# STM-Board-v1_1.net
KiCad netlist of a schematic drawn in Altium Designer
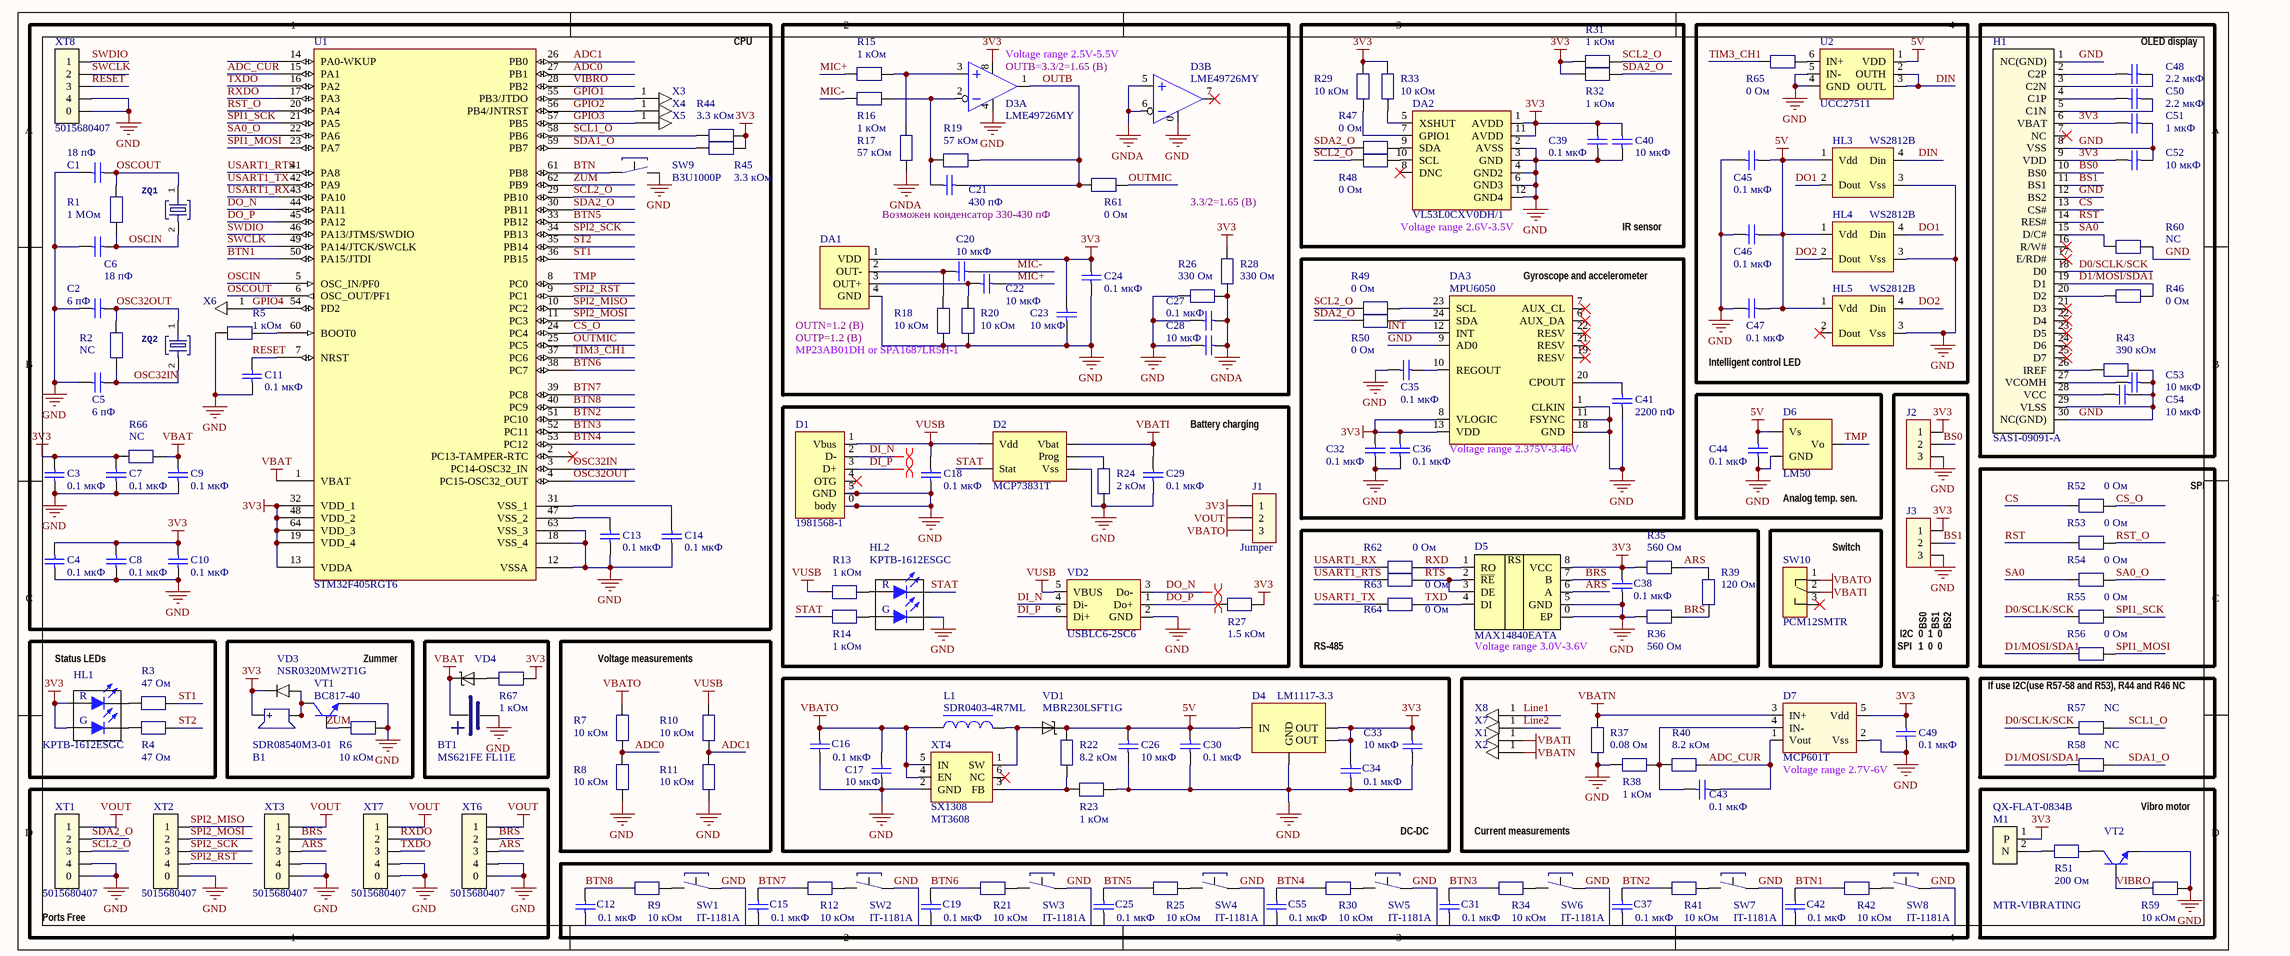
[diagram p0: STM-Board-v1.1.SchDoc]

(export (version "E")
  (design (tool "Eeschema 10.0.6"))
  (components
    (comp (ref "B1")
      (value "SDR08540M3-01")
      (footprint "SDR08540M3-01")
      (libsource (lib "dan") (part "SDR08540M3-01"))
    )
    (comp (ref "BT1")
      (value "MS621FE FL11E")
      (footprint "MS621FE FL11E")
      (libsource (lib "dan") (part "Battery RTC"))
    )
    (comp (ref "C1")
      (value "18 пФ")
      (footprint "C0402")
      (description "Чип конденсатор 0805")
      (fields (field (name "Comment") "Capacitor"))
      (libsource (lib "dan") (part "Capacitor"))
    )
    (comp (ref "C2")
      (value "6 пФ")
      (footprint "C0402")
      (description "Чип конденсатор 0805")
      (fields (field (name "Comment") "Capacitor"))
      (libsource (lib "dan") (part "Capacitor"))
    )
    (comp (ref "C3")
      (value "0.1 мкФ")
      (footprint "C0402")
      (description "Чип конденсатор 0805")
      (fields (field (name "Comment") "Capacitor"))
      (libsource (lib "dan") (part "Capacitor"))
    )
    (comp (ref "C4")
      (value "0.1 мкФ")
      (footprint "C0402")
      (description "Чип конденсатор 0805")
      (fields (field (name "Comment") "Capacitor"))
      (libsource (lib "dan") (part "Capacitor"))
    )
    (comp (ref "C5")
      (value "6 пФ")
      (footprint "C0402")
      (description "Чип конденсатор 0805")
      (fields (field (name "Comment") "Capacitor"))
      (libsource (lib "dan") (part "Capacitor"))
    )
    (comp (ref "C6")
      (value "18 пФ")
      (footprint "C0402")
      (description "Чип конденсатор 0805")
      (fields (field (name "Comment") "Capacitor"))
      (libsource (lib "dan") (part "Capacitor"))
    )
    (comp (ref "C7")
      (value "0.1 мкФ")
      (footprint "C0402")
      (description "Чип конденсатор 0805")
      (fields (field (name "Comment") "Capacitor"))
      (libsource (lib "dan") (part "Capacitor"))
    )
    (comp (ref "C8")
      (value "0.1 мкФ")
      (footprint "C0402")
      (description "Чип конденсатор 0805")
      (fields (field (name "Comment") "Capacitor"))
      (libsource (lib "dan") (part "Capacitor"))
    )
    (comp (ref "C9")
      (value "0.1 мкФ")
      (footprint "C0402")
      (description "Чип конденсатор 0805")
      (fields (field (name "Comment") "Capacitor"))
      (libsource (lib "dan") (part "Capacitor"))
    )
    (comp (ref "C10")
      (value "0.1 мкФ")
      (footprint "C0402")
      (description "Чип конденсатор 0805")
      (fields (field (name "Comment") "Capacitor"))
      (libsource (lib "dan") (part "Capacitor"))
    )
    (comp (ref "C11")
      (value "0.1 мкФ")
      (footprint "C0402")
      (description "Чип конденсатор 0805")
      (fields (field (name "Comment") "Capacitor"))
      (libsource (lib "dan") (part "Capacitor"))
    )
    (comp (ref "C12")
      (value "0.1 мкФ")
      (footprint "C0402")
      (description "Чип конденсатор 0805")
      (fields (field (name "Comment") "Capacitor"))
      (libsource (lib "dan") (part "Capacitor"))
    )
    (comp (ref "C13")
      (value "0.1 мкФ")
      (footprint "C0402")
      (description "Чип конденсатор 0805")
      (fields (field (name "Comment") "Capacitor"))
      (libsource (lib "dan") (part "Capacitor"))
    )
    (comp (ref "C14")
      (value "0.1 мкФ")
      (footprint "C0402")
      (description "Чип конденсатор 0805")
      (fields (field (name "Comment") "Capacitor"))
      (libsource (lib "dan") (part "Capacitor"))
    )
    (comp (ref "C15")
      (value "0.1 мкФ")
      (footprint "C0402")
      (description "Чип конденсатор 0805")
      (fields (field (name "Comment") "Capacitor"))
      (libsource (lib "dan") (part "Capacitor"))
    )
    (comp (ref "C16")
      (value "0.1 мкФ")
      (footprint "C0402")
      (description "Чип конденсатор 0805")
      (fields (field (name "Comment") "Capacitor"))
      (libsource (lib "dan") (part "Capacitor"))
    )
    (comp (ref "C17")
      (value "10 мкФ")
      (footprint "1206")
      (description "Чип конденсатор 0805")
      (fields (field (name "Comment") "Capacitor"))
      (libsource (lib "dan") (part "Capacitor"))
    )
    (comp (ref "C18")
      (value "0.1 мкФ")
      (footprint "C0402")
      (description "Чип конденсатор 0805")
      (fields (field (name "Comment") "Capacitor"))
      (libsource (lib "dan") (part "Capacitor"))
    )
    (comp (ref "C19")
      (value "0.1 мкФ")
      (footprint "C0402")
      (description "Чип конденсатор 0805")
      (fields (field (name "Comment") "Capacitor"))
      (libsource (lib "dan") (part "Capacitor"))
    )
    (comp (ref "C20")
      (value "10 мкФ")
      (footprint "C0402")
      (description "Чип конденсатор 0805")
      (fields (field (name "Comment") "Capacitor"))
      (libsource (lib "dan") (part "Capacitor"))
    )
    (comp (ref "C21")
      (value "430 пФ")
      (footprint "C0402")
      (description "Чип конденсатор 0805")
      (fields (field (name "Comment") "Capacitor"))
      (libsource (lib "dan") (part "Capacitor"))
    )
    (comp (ref "C22")
      (value "10 мкФ")
      (footprint "C0402")
      (description "Чип конденсатор 0805")
      (fields (field (name "Comment") "Capacitor"))
      (libsource (lib "dan") (part "Capacitor"))
    )
    (comp (ref "C23")
      (value "10 мкФ")
      (footprint "C0402")
      (description "Чип конденсатор 0805")
      (fields (field (name "Comment") "Capacitor"))
      (libsource (lib "dan") (part "Capacitor"))
    )
    (comp (ref "C24")
      (value "0.1 мкФ")
      (footprint "C0402")
      (description "Чип конденсатор 0805")
      (fields (field (name "Comment") "Capacitor"))
      (libsource (lib "dan") (part "Capacitor"))
    )
    (comp (ref "C25")
      (value "0.1 мкФ")
      (footprint "C0402")
      (description "Чип конденсатор 0805")
      (fields (field (name "Comment") "Capacitor"))
      (libsource (lib "dan") (part "Capacitor"))
    )
    (comp (ref "C26")
      (value "10 мкФ")
      (footprint "1206")
      (description "Чип конденсатор 0805")
      (fields (field (name "Comment") "Capacitor"))
      (libsource (lib "dan") (part "Capacitor"))
    )
    (comp (ref "C27")
      (value "0.1 мкФ")
      (footprint "C0402")
      (description "Чип конденсатор 0805")
      (fields (field (name "Comment") "Capacitor"))
      (libsource (lib "dan") (part "Capacitor"))
    )
    (comp (ref "C28")
      (value "10 мкФ")
      (footprint "C0402")
      (description "Чип конденсатор 0805")
      (fields (field (name "Comment") "Capacitor"))
      (libsource (lib "dan") (part "Capacitor"))
    )
    (comp (ref "C29")
      (value "0.1 мкФ")
      (footprint "C0402")
      (description "Чип конденсатор 0805")
      (fields (field (name "Comment") "Capacitor"))
      (libsource (lib "dan") (part "Capacitor"))
    )
    (comp (ref "C30")
      (value "0.1 мкФ")
      (footprint "C0402")
      (description "Чип конденсатор 0805")
      (fields (field (name "Comment") "Capacitor"))
      (libsource (lib "dan") (part "Capacitor"))
    )
    (comp (ref "C31")
      (value "0.1 мкФ")
      (footprint "C0402")
      (description "Чип конденсатор 0805")
      (fields (field (name "Comment") "Capacitor"))
      (libsource (lib "dan") (part "Capacitor"))
    )
    (comp (ref "C32")
      (value "0.1 мкФ")
      (footprint "C0402")
      (description "Чип конденсатор 0805")
      (fields (field (name "Comment") "Capacitor"))
      (libsource (lib "dan") (part "Capacitor"))
    )
    (comp (ref "C33")
      (value "10 мкФ")
      (footprint "1206")
      (description "Чип конденсатор 0805")
      (fields (field (name "Comment") "Capacitor"))
      (libsource (lib "dan") (part "Capacitor"))
    )
    (comp (ref "C34")
      (value "0.1 мкФ")
      (footprint "C0402")
      (description "Чип конденсатор 0805")
      (fields (field (name "Comment") "Capacitor"))
      (libsource (lib "dan") (part "Capacitor"))
    )
    (comp (ref "C35")
      (value "0.1 мкФ")
      (footprint "C0402")
      (description "Чип конденсатор 0805")
      (fields (field (name "Comment") "Capacitor"))
      (libsource (lib "dan") (part "Capacitor"))
    )
    (comp (ref "C36")
      (value "0.1 мкФ")
      (footprint "C0402")
      (description "Чип конденсатор 0805")
      (fields (field (name "Comment") "Capacitor"))
      (libsource (lib "dan") (part "Capacitor"))
    )
    (comp (ref "C37")
      (value "0.1 мкФ")
      (footprint "C0402")
      (description "Чип конденсатор 0805")
      (fields (field (name "Comment") "Capacitor"))
      (libsource (lib "dan") (part "Capacitor"))
    )
    (comp (ref "C38")
      (value "0.1 мкФ")
      (footprint "C0402")
      (description "Чип конденсатор 0805")
      (fields (field (name "Comment") "Capacitor"))
      (libsource (lib "dan") (part "Capacitor"))
    )
    (comp (ref "C39")
      (value "0.1 мкФ")
      (footprint "C0402")
      (description "Чип конденсатор 0805")
      (fields (field (name "Comment") "Capacitor"))
      (libsource (lib "dan") (part "Capacitor"))
    )
    (comp (ref "C40")
      (value "10 мкФ")
      (footprint "C0402")
      (description "Чип конденсатор 0805")
      (fields (field (name "Comment") "Capacitor"))
      (libsource (lib "dan") (part "Capacitor"))
    )
    (comp (ref "C41")
      (value "2200 пФ")
      (footprint "C0402")
      (description "Чип конденсатор 0805")
      (fields (field (name "Comment") "Capacitor"))
      (libsource (lib "dan") (part "Capacitor"))
    )
    (comp (ref "C42")
      (value "0.1 мкФ")
      (footprint "C0402")
      (description "Чип конденсатор 0805")
      (fields (field (name "Comment") "Capacitor"))
      (libsource (lib "dan") (part "Capacitor"))
    )
    (comp (ref "C43")
      (value "0.1 мкФ")
      (footprint "C0402")
      (description "Чип конденсатор 0805")
      (fields (field (name "Comment") "Capacitor"))
      (libsource (lib "dan") (part "Capacitor"))
    )
    (comp (ref "C44")
      (value "0.1 мкФ")
      (footprint "C0402")
      (description "Чип конденсатор 0805")
      (fields (field (name "Comment") "Capacitor"))
      (libsource (lib "dan") (part "Capacitor"))
    )
    (comp (ref "C45")
      (value "0.1 мкФ")
      (footprint "C0402")
      (description "Чип конденсатор 0805")
      (fields (field (name "Comment") "Capacitor"))
      (libsource (lib "dan") (part "Capacitor"))
    )
    (comp (ref "C46")
      (value "0.1 мкФ")
      (footprint "C0402")
      (description "Чип конденсатор 0805")
      (fields (field (name "Comment") "Capacitor"))
      (libsource (lib "dan") (part "Capacitor"))
    )
    (comp (ref "C47")
      (value "0.1 мкФ")
      (footprint "C0402")
      (description "Чип конденсатор 0805")
      (fields (field (name "Comment") "Capacitor"))
      (libsource (lib "dan") (part "Capacitor"))
    )
    (comp (ref "C48")
      (value "2.2 мкФ")
      (footprint "C0402")
      (description "Чип конденсатор 0805")
      (fields (field (name "Comment") "Capacitor"))
      (libsource (lib "dan") (part "Capacitor"))
    )
    (comp (ref "C49")
      (value "0.1 мкФ")
      (footprint "C0402")
      (description "Чип конденсатор 0805")
      (fields (field (name "Comment") "Capacitor"))
      (libsource (lib "dan") (part "Capacitor"))
    )
    (comp (ref "C50")
      (value "2.2 мкФ")
      (footprint "C0402")
      (description "Чип конденсатор 0805")
      (fields (field (name "Comment") "Capacitor"))
      (libsource (lib "dan") (part "Capacitor"))
    )
    (comp (ref "C51")
      (value "1 мкФ")
      (footprint "C0402")
      (description "Чип конденсатор 0805")
      (fields (field (name "Comment") "Capacitor"))
      (libsource (lib "dan") (part "Capacitor"))
    )
    (comp (ref "C52")
      (value "10 мкФ")
      (footprint "C0402")
      (description "Чип конденсатор 0805")
      (fields (field (name "Comment") "Capacitor"))
      (libsource (lib "dan") (part "Capacitor"))
    )
    (comp (ref "C53")
      (value "10 мкФ")
      (footprint "C0402")
      (description "Чип конденсатор 0805")
      (fields (field (name "Comment") "Capacitor"))
      (libsource (lib "dan") (part "Capacitor"))
    )
    (comp (ref "C54")
      (value "10 мкФ")
      (footprint "C0402")
      (description "Чип конденсатор 0805")
      (fields (field (name "Comment") "Capacitor"))
      (libsource (lib "dan") (part "Capacitor"))
    )
    (comp (ref "C55")
      (value "0.1 мкФ")
      (footprint "C0402")
      (description "Чип конденсатор 0805")
      (fields (field (name "Comment") "Capacitor"))
      (libsource (lib "dan") (part "Capacitor"))
    )
    (comp (ref "D1")
      (value "1981568-1")
      (footprint "MicroUSB-B")
      (description "micro")
      (libsource (lib "dan") (part "USB_micro"))
    )
    (comp (ref "D2") (value "MCP73831T") (footprint "SOT23-5") (libsource (lib "dan") (part "MCP73831")))
    (comp (ref "D3")
      (value "LME49726MY")
      (footprint "MSOP8 - PP")
      (description "Comparators")
      (fields (field (name "Comment") "Audio Operational Amplifier"))
      (libsource (lib "dan") (part "LME49726"))
    )
    (comp (ref "D4") (value "LM1117-3.3") (footprint "SOT223") (libsource (lib "dan") (part "LM1117")))
    (comp (ref "D5")
      (value "MAX14840EATA")
      (footprint "TDFN-8")
      (description "RS-485")
      (libsource (lib "dan") (part "MAX14840"))
    )
    (comp (ref "D6")
      (value "LM50")
      (footprint "SOT-23")
      (description "Temperatury sensors")
      (fields (field (name "Comment") "Датчик температуры"))
      (libsource (lib "dan") (part "LM50"))
    )
    (comp (ref "D7")
      (value "MCP601T")
      (footprint "SOT23-5")
      (fields (field (name "Comment") "Операционный усилитель"))
      (libsource (lib "dan") (part "MCP601T"))
    )
    (comp (ref "DA1")
      (value "MP23AB01DH or SPA1687LR5H-1")
      (footprint "MP23AB01DH")
      (libsource (lib "dan") (part "MP23AB01DH"))
    )
    (comp (ref "DA2")
      (value "VL53L0CXV0DH/1")
      (footprint "dan:VL53L0X - big")
      (fields (field (name "Comment") "ИК датчик VL53L0X"))
      (libsource (lib "dan") (part "VL53L0X"))
    )
    (comp (ref "DA3")
      (value "MPU6050")
      (footprint "MPU-6050")
      (fields (field (name "Comment") "Гироскоп"))
      (libsource (lib "dan") (part "MPU6050"))
    )
    (comp (ref "H1")
      (value "SAS1-09091-A")
      (footprint "OLED 1.3 128x64")
      (description "1.3in OLED 128x64  SAS1-09091-A")
      (fields (field (name "Comment") "OLED DIsp 1.3 128x64"))
      (libsource (lib "dan") (part "OLED_1.3_128x64"))
    )
    (comp (ref "HL1")
      (value "KPTB-1612ESGC")
      (footprint "LED_1.6x1.25")
      (libsource (lib "dan") (part "LED_x2_RG"))
    )
    (comp (ref "HL2")
      (value "KPTB-1612ESGC")
      (footprint "LED_1.6x1.25")
      (libsource (lib "dan") (part "LED_x2_RG"))
    )
    (comp (ref "HL3") (value "WS2812B") (footprint "WS2812B_N") (libsource (lib "dan") (part "WS2812B")))
    (comp (ref "HL4") (value "WS2812B") (footprint "WS2812B_N") (libsource (lib "dan") (part "WS2812B")))
    (comp (ref "HL5") (value "WS2812B") (footprint "WS2812B_N") (libsource (lib "dan") (part "WS2812B")))
    (comp (ref "J1")
      (value "Jumper")
      (footprint "Jumper_3")
      (fields (field (name "Comment") "Jumper_2"))
      (libsource (lib "") (part "Jumper_2_1"))
    )
    (comp (ref "J2")
      (value "Jumper_2")
      (footprint "Jumper_3")
      (description "Jumper")
      (libsource (lib "dan") (part "Jumper_2"))
    )
    (comp (ref "J3")
      (value "Jumper_2")
      (footprint "Jumper_3")
      (description "Jumper")
      (libsource (lib "dan") (part "Jumper_2"))
    )
    (comp (ref "L1") (value "SDR0403-4R7ML") (footprint "SDR0403") (libsource (lib "dan") (part "inductor")))
    (comp (ref "M1")
      (value "QX-FLAT-0834B")
      (footprint "QX-FLAT-0834B")
      (description "VIBRATING")
      (libsource (lib "dan") (part "QX-FLAT-0834B"))
    )
    (comp (ref "R1")
      (value "1 МОм")
      (footprint "R0402")
      (fields (field (name "Comment") "Чип резистор"))
      (libsource (lib "") (part "Resistor_2"))
    )
    (comp (ref "R2")
      (value "NC")
      (footprint "R0402")
      (fields (field (name "Comment") "Чип резистор"))
      (libsource (lib "") (part "Resistor_1"))
    )
    (comp (ref "R3")
      (value "47 Ом")
      (footprint "R0402")
      (fields (field (name "Comment") "Чип резистор 0402"))
      (libsource (lib "dan") (part "Resistor"))
    )
    (comp (ref "R4")
      (value "47 Ом")
      (footprint "R0402")
      (fields (field (name "Comment") "Чип резистор 0402"))
      (libsource (lib "dan") (part "Resistor"))
    )
    (comp (ref "R5")
      (value "1 кОм")
      (footprint "R0402")
      (fields (field (name "Comment") "Чип резистор"))
      (libsource (lib "") (part "Resistor_3"))
    )
    (comp (ref "R6")
      (value "10 кОм")
      (footprint "R0402")
      (fields (field (name "Comment") "Чип резистор"))
      (libsource (lib "") (part "Resistor_3"))
    )
    (comp (ref "R7")
      (value "10 кОм")
      (footprint "R0402")
      (fields (field (name "Comment") "Чип резистор"))
      (libsource (lib "") (part "Resistor_1"))
    )
    (comp (ref "R8")
      (value "10 кОм")
      (footprint "R0402")
      (fields (field (name "Comment") "Чип резистор"))
      (libsource (lib "") (part "Resistor_1"))
    )
    (comp (ref "R9")
      (value "10 кОм")
      (footprint "R0402")
      (fields (field (name "Comment") "Чип резистор"))
      (libsource (lib "dan") (part "Resistor"))
    )
    (comp (ref "R10")
      (value "10 кОм")
      (footprint "R0402")
      (fields (field (name "Comment") "Чип резистор"))
      (libsource (lib "") (part "Resistor_1"))
    )
    (comp (ref "R11")
      (value "10 кОм")
      (footprint "R0402")
      (fields (field (name "Comment") "Чип резистор"))
      (libsource (lib "") (part "Resistor_1"))
    )
    (comp (ref "R12")
      (value "10 кОм")
      (footprint "R0402")
      (fields (field (name "Comment") "Чип резистор"))
      (libsource (lib "dan") (part "Resistor"))
    )
    (comp (ref "R13")
      (value "1 кОм")
      (footprint "R0402")
      (description "Чип резистор 0402")
      (libsource (lib "dan") (part "R0402"))
    )
    (comp (ref "R14")
      (value "1 кОм")
      (footprint "R0402")
      (description "Чип резистор 0402")
      (libsource (lib "dan") (part "R0402"))
    )
    (comp (ref "R15")
      (value "1 кОм")
      (footprint "R0402")
      (fields (field (name "Comment") "Чип резистор"))
      (libsource (lib "dan") (part "Resistor"))
    )
    (comp (ref "R16")
      (value "1 кОм")
      (footprint "R0402")
      (fields (field (name "Comment") "Чип резистор"))
      (libsource (lib "dan") (part "Resistor"))
    )
    (comp (ref "R17")
      (value "57 кОм")
      (footprint "R0402")
      (fields (field (name "Comment") "Чип резистор"))
      (libsource (lib "") (part "Resistor_2"))
    )
    (comp (ref "R18")
      (value "10 кОм")
      (footprint "R0402")
      (fields (field (name "Comment") "Чип резистор"))
      (libsource (lib "") (part "Resistor_1"))
    )
    (comp (ref "R19")
      (value "57 кОм")
      (footprint "R0402")
      (fields (field (name "Comment") "Чип резистор"))
      (libsource (lib "dan") (part "Resistor"))
    )
    (comp (ref "R20")
      (value "10 кОм")
      (footprint "R0402")
      (fields (field (name "Comment") "Чип резистор"))
      (libsource (lib "") (part "Resistor_1"))
    )
    (comp (ref "R21")
      (value "10 кОм")
      (footprint "R0402")
      (fields (field (name "Comment") "Чип резистор"))
      (libsource (lib "dan") (part "Resistor"))
    )
    (comp (ref "R22")
      (value "8.2 кОм")
      (footprint "R0402")
      (description "Чип резистор 0402")
      (libsource (lib "") (part "R0402_1"))
    )
    (comp (ref "R23")
      (value "1 кОм")
      (footprint "R0402")
      (description "Чип резистор 0402")
      (libsource (lib "dan") (part "R0402"))
    )
    (comp (ref "R24")
      (value "2 кОм")
      (footprint "R0402")
      (fields (field (name "Comment") "Чип резистор"))
      (libsource (lib "") (part "Resistor_2"))
    )
    (comp (ref "R25")
      (value "10 кОм")
      (footprint "R0402")
      (fields (field (name "Comment") "Чип резистор"))
      (libsource (lib "dan") (part "Resistor"))
    )
    (comp (ref "R26")
      (value "330 Ом")
      (footprint "R0402")
      (fields (field (name "Comment") "Чип резистор"))
      (libsource (lib "dan") (part "Resistor"))
    )
    (comp (ref "R27")
      (value "1.5 кОм")
      (footprint "R0402")
      (fields (field (name "Comment") "Чип резистор"))
      (libsource (lib "dan") (part "Resistor"))
    )
    (comp (ref "R28")
      (value "330 Ом")
      (footprint "R0402")
      (fields (field (name "Comment") "Чип резистор"))
      (libsource (lib "") (part "Resistor_2"))
    )
    (comp (ref "R29")
      (value "10 кОм")
      (footprint "R0402")
      (fields (field (name "Comment") "Чип резистор"))
      (libsource (lib "") (part "Resistor_2"))
    )
    (comp (ref "R30")
      (value "10 кОм")
      (footprint "R0402")
      (fields (field (name "Comment") "Чип резистор"))
      (libsource (lib "dan") (part "Resistor"))
    )
    (comp (ref "R31")
      (value "1 кОм")
      (footprint "R0402")
      (fields (field (name "Comment") "Чип резистор"))
      (libsource (lib "") (part "Resistor_3"))
    )
    (comp (ref "R32")
      (value "1 кОм")
      (footprint "R0402")
      (fields (field (name "Comment") "Чип резистор"))
      (libsource (lib "") (part "Resistor_3"))
    )
    (comp (ref "R33")
      (value "10 кОм")
      (footprint "R0402")
      (fields (field (name "Comment") "Чип резистор"))
      (libsource (lib "") (part "Resistor_2"))
    )
    (comp (ref "R34")
      (value "10 кОм")
      (footprint "R0402")
      (fields (field (name "Comment") "Чип резистор"))
      (libsource (lib "dan") (part "Resistor"))
    )
    (comp (ref "R35")
      (value "560 Ом")
      (footprint "R0402")
      (fields (field (name "Comment") "Чип резистор"))
      (libsource (lib "") (part "Resistor_3"))
    )
    (comp (ref "R36")
      (value "560 Ом")
      (footprint "R0402")
      (fields (field (name "Comment") "Чип резистор"))
      (libsource (lib "") (part "Resistor_3"))
    )
    (comp (ref "R37")
      (value "0.08 Ом")
      (footprint "P1206")
      (fields (field (name "Comment") "Чип резистор"))
      (libsource (lib "") (part "Resistor_1"))
    )
    (comp (ref "R38")
      (value "1 кОм")
      (footprint "R0402")
      (fields (field (name "Comment") "Чип резистор"))
      (libsource (lib "") (part "Resistor_3"))
    )
    (comp (ref "R39")
      (value "120 Ом")
      (footprint "R0402")
      (fields (field (name "Comment") "Чип резистор"))
      (libsource (lib "") (part "Resistor_1"))
    )
    (comp (ref "R40")
      (value "8.2 кОм")
      (footprint "R0402")
      (fields (field (name "Comment") "Чип резистор"))
      (libsource (lib "") (part "Resistor_3"))
    )
    (comp (ref "R41")
      (value "10 кОм")
      (footprint "R0402")
      (fields (field (name "Comment") "Чип резистор"))
      (libsource (lib "dan") (part "Resistor"))
    )
    (comp (ref "R42")
      (value "10 кОм")
      (footprint "R0402")
      (fields (field (name "Comment") "Чип резистор"))
      (libsource (lib "dan") (part "Resistor"))
    )
    (comp (ref "R43")
      (value "390 кОм")
      (footprint "R0402")
      (fields (field (name "Comment") "Чип резистор"))
      (libsource (lib "") (part "Resistor_3"))
    )
    (comp (ref "R44")
      (value "3.3 кОм")
      (footprint "R0402")
      (fields (field (name "Comment") "Чип резистор"))
      (libsource (lib "") (part "Resistor_2"))
    )
    (comp (ref "R45")
      (value "3.3 кОм")
      (footprint "R0402")
      (fields (field (name "Comment") "Чип резистор"))
      (libsource (lib "") (part "Resistor_2"))
    )
    (comp (ref "R46")
      (value "0 Ом")
      (footprint "R0402")
      (fields (field (name "Comment") "Чип резистор"))
      (libsource (lib "") (part "Resistor_3"))
    )
    (comp (ref "R47")
      (value "0 Ом")
      (footprint "R0402")
      (fields (field (name "Comment") "Чип резистор"))
      (libsource (lib "") (part "Resistor_3"))
    )
    (comp (ref "R48")
      (value "0 Ом")
      (footprint "R0402")
      (fields (field (name "Comment") "Чип резистор"))
      (libsource (lib "") (part "Resistor_3"))
    )
    (comp (ref "R49")
      (value "0 Ом")
      (footprint "R0402")
      (fields (field (name "Comment") "Чип резистор"))
      (libsource (lib "") (part "Resistor_3"))
    )
    (comp (ref "R50")
      (value "0 Ом")
      (footprint "R0402")
      (fields (field (name "Comment") "Чип резистор"))
      (libsource (lib "") (part "Resistor_3"))
    )
    (comp (ref "R51")
      (value "200 Ом")
      (footprint "R0402")
      (fields (field (name "Comment") "Чип резистор"))
      (libsource (lib "dan") (part "Resistor"))
    )
    (comp (ref "R52")
      (value "0 Ом")
      (footprint "R0402")
      (fields (field (name "Comment") "Чип резистор"))
      (libsource (lib "") (part "Resistor_3"))
    )
    (comp (ref "R53")
      (value "0 Ом")
      (footprint "R0402")
      (fields (field (name "Comment") "Чип резистор"))
      (libsource (lib "") (part "Resistor_3"))
    )
    (comp (ref "R54")
      (value "0 Ом")
      (footprint "R0402")
      (fields (field (name "Comment") "Чип резистор"))
      (libsource (lib "") (part "Resistor_3"))
    )
    (comp (ref "R55")
      (value "0 Ом")
      (footprint "R0402")
      (fields (field (name "Comment") "Чип резистор"))
      (libsource (lib "") (part "Resistor_3"))
    )
    (comp (ref "R56")
      (value "0 Ом")
      (footprint "R0402")
      (fields (field (name "Comment") "Чип резистор"))
      (libsource (lib "") (part "Resistor_3"))
    )
    (comp (ref "R57")
      (value "NC")
      (footprint "R0402")
      (fields (field (name "Comment") "Чип резистор"))
      (libsource (lib "") (part "Resistor_3"))
    )
    (comp (ref "R58")
      (value "NC")
      (footprint "R0402")
      (fields (field (name "Comment") "Чип резистор"))
      (libsource (lib "") (part "Resistor_3"))
    )
    (comp (ref "R59")
      (value "10 кОм")
      (footprint "R0402")
      (fields (field (name "Comment") "Чип резистор"))
      (libsource (lib "dan") (part "Resistor"))
    )
    (comp (ref "R60")
      (value "NC")
      (footprint "R0402")
      (fields (field (name "Comment") "Чип резистор"))
      (libsource (lib "") (part "Resistor_3"))
    )
    (comp (ref "R61")
      (value "0 Ом")
      (footprint "R0402")
      (fields (field (name "Comment") "Чип резистор"))
      (libsource (lib "") (part "Resistor_3"))
    )
    (comp (ref "R62")
      (value "0 Ом")
      (footprint "R0402")
      (fields (field (name "Comment") "Чип резистор"))
      (libsource (lib "") (part "Resistor_3"))
    )
    (comp (ref "R63")
      (value "0 Ом")
      (footprint "R0402")
      (fields (field (name "Comment") "Чип резистор"))
      (libsource (lib "") (part "Resistor_3"))
    )
    (comp (ref "R64")
      (value "0 Ом")
      (footprint "R0402")
      (fields (field (name "Comment") "Чип резистор"))
      (libsource (lib "") (part "Resistor_3"))
    )
    (comp (ref "R65")
      (value "0 Ом")
      (footprint "R0402")
      (fields (field (name "Comment") "Чип резистор"))
      (libsource (lib "") (part "Resistor_3"))
    )
    (comp (ref "R66")
      (value "NC")
      (footprint "R0402")
      (fields (field (name "Comment") "Чип резистор"))
      (libsource (lib "dan") (part "Resistor"))
    )
    (comp (ref "R67")
      (value "1 кОм")
      (footprint "R0402")
      (fields (field (name "Comment") "Чип резистор"))
      (libsource (lib "") (part "Resistor_3"))
    )
    (comp (ref "SW1") (value "IT-1181A") (footprint "SWT-1") (libsource (lib "dan") (part "SWT-1-1")))
    (comp (ref "SW2") (value "IT-1181A") (footprint "SWT-1") (libsource (lib "dan") (part "SWT-1-1")))
    (comp (ref "SW3") (value "IT-1181A") (footprint "SWT-1") (libsource (lib "dan") (part "SWT-1-1")))
    (comp (ref "SW4") (value "IT-1181A") (footprint "SWT-1") (libsource (lib "dan") (part "SWT-1-1")))
    (comp (ref "SW5") (value "IT-1181A") (footprint "SWT-1") (libsource (lib "dan") (part "SWT-1-1")))
    (comp (ref "SW6") (value "IT-1181A") (footprint "SWT-1") (libsource (lib "dan") (part "SWT-1-1")))
    (comp (ref "SW7") (value "IT-1181A") (footprint "SWT-1") (libsource (lib "dan") (part "SWT-1-1")))
    (comp (ref "SW8") (value "IT-1181A") (footprint "SWT-1") (libsource (lib "dan") (part "SWT-1-1")))
    (comp (ref "SW9") (value "B3U1000P") (footprint "B3U1000P") (libsource (lib "dan") (part "SWT-1_1")))
    (comp (ref "SW10") (value "PCM12SMTR") (footprint "PCM12SMTR") (libsource (lib "dan") (part "PCM12SMTR")))
    (comp (ref "U1")
      (value "STM32F405RGT6")
      (footprint "LQFP64_L")
      (description "STM32 ARM-Cortex M3 32-bit MCU, 128 kB")
      (fields (field (name "Comment") "STM32F302RCT6"))
      (libsource (lib "dan") (part "STM32F302R"))
    )
    (comp (ref "U2") (value "UCC27511") (footprint "SOT23-6") (libsource (lib "dan") (part "UCC27511")))
    (comp (ref "VD1")
      (value "MBR230LSFT1G")
      (footprint "SOD-123")
      (description "Diod schottki")
      (libsource (lib "dan") (part "MBR120LSFT1G"))
    )
    (comp (ref "VD2")
      (value "USBLC6-2SC6")
      (footprint "SOT23-6")
      (description "ESD")
      (libsource (lib "dan") (part "USBLC6-2SC6"))
    )
    (comp (ref "VD3")
      (value "NSR0320MW2T1G")
      (footprint "SOD-323")
      (description "Диод")
      (libsource (lib "dan") (part "diode"))
    )
    (comp (ref "VD4")
      (value "NSR0320MW2T1G")
      (footprint "SOD-323")
      (description "Diod schottki")
      (libsource (lib "dan") (part "MBR120LSFT1G"))
    )
    (comp (ref "VT1")
      (value "ВС817-40")
      (footprint "SOT-23")
      (description "BC817-40 NPN Транзистор")
      (libsource (lib "dan") (part "BC817-40"))
    )
    (comp (ref "VT2")
      (value "ВС817-40")
      (footprint "SOT-23")
      (description "BC817-40 NPN Транзистор")
      (libsource (lib "dan") (part "BC817-40"))
    )
    (comp (ref "X1") (value "~") (footprint "PAD_1X2") (libsource (lib "dan") (part "Pad")))
    (comp (ref "X2") (value "~") (footprint "PAD_1X2") (libsource (lib "dan") (part "Pad")))
    (comp (ref "X3") (value "~") (footprint "Pad_R2") (libsource (lib "dan") (part "Pad")))
    (comp (ref "X4") (value "~") (footprint "Pad_R2") (libsource (lib "dan") (part "Pad")))
    (comp (ref "X5") (value "~") (footprint "Pad_R2") (libsource (lib "dan") (part "Pad")))
    (comp (ref "X6") (value "~") (footprint "Pad_R2") (libsource (lib "dan") (part "Pad")))
    (comp (ref "X7") (value "~") (footprint "Pad_R2") (libsource (lib "dan") (part "Pad")))
    (comp (ref "X8") (value "~") (footprint "Pad_R2") (libsource (lib "dan") (part "Pad")))
    (comp (ref "XT1")
      (value "5015680407")
      (footprint "5015680407")
      (description "molex")
      (libsource (lib "dan") (part "5015680407"))
    )
    (comp (ref "XT2")
      (value "5015680407")
      (footprint "5015680407")
      (description "molex")
      (libsource (lib "dan") (part "5015680407"))
    )
    (comp (ref "XT3")
      (value "5015680407")
      (footprint "5015680407")
      (description "molex")
      (libsource (lib "dan") (part "5015680407"))
    )
    (comp (ref "XT4")
      (value "SX1308")
      (footprint "SOT23-6")
      (description "DC-DC Step_Up")
      (libsource (lib "dan") (part "SX1308"))
    )
    (comp (ref "XT6")
      (value "5015680407")
      (footprint "5015680407")
      (description "molex")
      (libsource (lib "dan") (part "5015680407"))
    )
    (comp (ref "XT7")
      (value "5015680407")
      (footprint "5015680407")
      (description "molex")
      (libsource (lib "dan") (part "5015680407"))
    )
    (comp (ref "XT8")
      (value "5015680407")
      (footprint "5015680407")
      (description "molex")
      (libsource (lib "dan") (part "5015680407"))
    )
    (comp (ref "ZQ1")
      (value "ABM3-8.000MHZ-D2Y-T")
      (footprint "ABM3")
      (description "SMD Quartz")
      (libsource (lib "dan") (part "ABM3"))
    )
    (comp (ref "ZQ2")
      (value "ABS07-120-32.768KHZ-T")
      (footprint "ABS07")
      (description "SMD Quartz")
      (libsource (lib "dan") (part "ABM3"))
    )
  )
  (nets
    (net (code "1") (name "/ADC0") (class "Default")
      (node (ref "R7") (pin "2") (pinfunction "2_2") (pintype "passive"))
      (node (ref "R8") (pin "1") (pinfunction "1_1") (pintype "passive"))
      (node (ref "U1") (pin "27") (pinfunction "PB1_27") (pintype "bidirectional"))
    )
    (net (code "2") (name "/ADC1") (class "Default")
      (node (ref "R10") (pin "2") (pinfunction "2_2") (pintype "passive"))
      (node (ref "R11") (pin "1") (pinfunction "1_1") (pintype "passive"))
      (node (ref "U1") (pin "26") (pinfunction "PB0_26") (pintype "bidirectional"))
    )
    (net (code "3") (name "/ADC_CUR") (class "Default")
      (node (ref "C43") (pin "1") (pinfunction "1_1") (pintype "passive"))
      (node (ref "D7") (pin "1") (pinfunction "Vout_1") (pintype "passive"))
      (node (ref "R40") (pin "1") (pinfunction "1_1") (pintype "passive"))
      (node (ref "U1") (pin "15") (pinfunction "PA1_15") (pintype "bidirectional"))
    )
    (net (code "4") (name "/ARS") (class "Default")
      (node (ref "D5") (pin "6") (pinfunction "A_6") (pintype "passive"))
      (node (ref "R35") (pin "1") (pinfunction "1_1") (pintype "passive"))
      (node (ref "R39") (pin "1") (pinfunction "1_1") (pintype "passive"))
      (node (ref "XT3") (pin "3") (pinfunction "3_3") (pintype "passive"))
      (node (ref "XT6") (pin "3") (pinfunction "3_3") (pintype "passive"))
    )
    (net (code "5") (name "/BRS") (class "Default")
      (node (ref "D5") (pin "7") (pinfunction "B_7") (pintype "passive"))
      (node (ref "R36") (pin "1") (pinfunction "1_1") (pintype "passive"))
      (node (ref "R39") (pin "2") (pinfunction "2_2") (pintype "passive"))
      (node (ref "XT3") (pin "2") (pinfunction "2_2") (pintype "passive"))
      (node (ref "XT6") (pin "2") (pinfunction "2_2") (pintype "passive"))
    )
    (net (code "6") (name "/BS0") (class "Default")
      (node (ref "H1") (pin "10") (pinfunction "BS0_10") (pintype "passive"))
      (node (ref "J2") (pin "2") (pinfunction "2_2") (pintype "passive"))
    )
    (net (code "7") (name "/BS1") (class "Default")
      (node (ref "H1") (pin "11") (pinfunction "BS1_11") (pintype "passive"))
      (node (ref "J3") (pin "2") (pinfunction "2_2") (pintype "passive"))
    )
    (net (code "8") (name "/BTN") (class "Default")
      (node (ref "SW9") (pin "1") (pinfunction "1_1") (pintype "passive"))
      (node (ref "U1") (pin "61") (pinfunction "PB8_61") (pintype "bidirectional"))
    )
    (net (code "9") (name "/BTN1") (class "Default")
      (node (ref "C42") (pin "2") (pinfunction "2_2") (pintype "passive"))
      (node (ref "R42") (pin "1") (pinfunction "1_1") (pintype "passive"))
      (node (ref "U1") (pin "50") (pinfunction "PA15/JTDI_50") (pintype "bidirectional"))
    )
    (net (code "10") (name "/BTN2") (class "Default")
      (node (ref "C37") (pin "2") (pinfunction "2_2") (pintype "passive"))
      (node (ref "R41") (pin "1") (pinfunction "1_1") (pintype "passive"))
      (node (ref "U1") (pin "51") (pinfunction "PC10_51") (pintype "bidirectional"))
    )
    (net (code "11") (name "/BTN3") (class "Default")
      (node (ref "C31") (pin "2") (pinfunction "2_2") (pintype "passive"))
      (node (ref "R34") (pin "1") (pinfunction "1_1") (pintype "passive"))
      (node (ref "U1") (pin "52") (pinfunction "PC11_52") (pintype "bidirectional"))
    )
    (net (code "12") (name "/BTN4") (class "Default")
      (node (ref "C55") (pin "2") (pinfunction "2_2") (pintype "passive"))
      (node (ref "R30") (pin "1") (pinfunction "1_1") (pintype "passive"))
      (node (ref "U1") (pin "53") (pinfunction "PC12_53") (pintype "bidirectional"))
    )
    (net (code "13") (name "/BTN5") (class "Default")
      (node (ref "C25") (pin "2") (pinfunction "2_2") (pintype "passive"))
      (node (ref "R25") (pin "1") (pinfunction "1_1") (pintype "passive"))
      (node (ref "U1") (pin "33") (pinfunction "PB12_33") (pintype "bidirectional"))
    )
    (net (code "14") (name "/BTN6") (class "Default")
      (node (ref "C19") (pin "2") (pinfunction "2_2") (pintype "passive"))
      (node (ref "R21") (pin "1") (pinfunction "1_1") (pintype "passive"))
      (node (ref "U1") (pin "38") (pinfunction "PC7_38") (pintype "bidirectional"))
    )
    (net (code "15") (name "/BTN7") (class "Default")
      (node (ref "C15") (pin "2") (pinfunction "2_2") (pintype "passive"))
      (node (ref "R12") (pin "1") (pinfunction "1_1") (pintype "passive"))
      (node (ref "U1") (pin "39") (pinfunction "PC8_39") (pintype "bidirectional"))
    )
    (net (code "16") (name "/BTN8") (class "Default")
      (node (ref "C12") (pin "2") (pinfunction "2_2") (pintype "passive"))
      (node (ref "R9") (pin "1") (pinfunction "1_1") (pintype "passive"))
      (node (ref "U1") (pin "40") (pinfunction "PC9_40") (pintype "bidirectional"))
    )
    (net (code "17") (name "/CS") (class "Default")
      (node (ref "H1") (pin "13") (pinfunction "CS#_13") (pintype "passive"))
      (node (ref "R52") (pin "2") (pinfunction "2_2") (pintype "passive"))
    )
    (net (code "18") (name "/CS_O") (class "Default")
      (node (ref "R52") (pin "1") (pinfunction "1_1") (pintype "passive"))
      (node (ref "U1") (pin "24") (pinfunction "PC4_24") (pintype "bidirectional"))
    )
    (net (code "19") (name "/D0{slash}SCLK{slash}SCK") (class "Default")
      (node (ref "H1") (pin "18") (pinfunction "D0_18") (pintype "passive"))
      (node (ref "R55") (pin "2") (pinfunction "2_2") (pintype "passive"))
      (node (ref "R57") (pin "2") (pinfunction "2_2") (pintype "passive"))
    )
    (net (code "20") (name "/D1{slash}MOSI{slash}SDA1") (class "Default")
      (node (ref "H1") (pin "19") (pinfunction "D1_19") (pintype "passive"))
      (node (ref "R46") (pin "1") (pinfunction "1_1") (pintype "passive"))
      (node (ref "R56") (pin "2") (pinfunction "2_2") (pintype "passive"))
      (node (ref "R58") (pin "2") (pinfunction "2_2") (pintype "passive"))
    )
    (net (code "21") (name "/DIN") (class "Default")
      (node (ref "HL3") (pin "4") (pinfunction "Din_4") (pintype "passive"))
      (node (ref "U2") (pin "2") (pinfunction "OUTH_2") (pintype "power_in"))
      (node (ref "U2") (pin "3") (pinfunction "OUTL_3") (pintype "power_in"))
    )
    (net (code "22") (name "/DI_N") (class "Default")
      (node (ref "D1") (pin "2") (pinfunction "D-_2") (pintype "passive"))
      (node (ref "VD2") (pin "4") (pinfunction "Di-_4") (pintype "power_in"))
    )
    (net (code "23") (name "/DI_P") (class "Default")
      (node (ref "D1") (pin "3") (pinfunction "D+_3") (pintype "passive"))
      (node (ref "VD2") (pin "6") (pinfunction "Di+_6") (pintype "passive"))
    )
    (net (code "24") (name "/DO1") (class "Default")
      (node (ref "HL3") (pin "2") (pinfunction "Dout_2") (pintype "passive"))
      (node (ref "HL4") (pin "4") (pinfunction "Din_4") (pintype "passive"))
    )
    (net (code "25") (name "/DO2") (class "Default")
      (node (ref "HL4") (pin "2") (pinfunction "Dout_2") (pintype "passive"))
      (node (ref "HL5") (pin "4") (pinfunction "Din_4") (pintype "passive"))
    )
    (net (code "26") (name "/DO_N") (class "Default")
      (node (ref "U1") (pin "44") (pinfunction "PA11_44") (pintype "bidirectional"))
      (node (ref "VD2") (pin "3") (pinfunction "Do-_3") (pintype "power_in"))
    )
    (net (code "27") (name "/DO_P") (class "Default")
      (node (ref "R27") (pin "1") (pinfunction "1_1") (pintype "passive"))
      (node (ref "U1") (pin "45") (pinfunction "PA12_45") (pintype "bidirectional"))
      (node (ref "VD2") (pin "1") (pinfunction "Do+_1") (pintype "power_in"))
    )
    (net (code "28") (name "/GPIO1") (class "Default")
      (node (ref "U1") (pin "55") (pinfunction "PB3/JTDO_55") (pintype "bidirectional"))
      (node (ref "X3") (pin "1") (pinfunction "1_1") (pintype "passive"))
    )
    (net (code "29") (name "/GPIO2") (class "Default")
      (node (ref "U1") (pin "56") (pinfunction "PB4/JNTRST_56") (pintype "bidirectional"))
      (node (ref "X4") (pin "1") (pinfunction "1_1") (pintype "passive"))
    )
    (net (code "30") (name "/GPIO3") (class "Default")
      (node (ref "U1") (pin "57") (pinfunction "PB5_57") (pintype "bidirectional"))
      (node (ref "X5") (pin "1") (pinfunction "1_1") (pintype "passive"))
    )
    (net (code "31") (name "/GPIO4") (class "Default")
      (node (ref "U1") (pin "54") (pinfunction "PD2_54") (pintype "bidirectional"))
      (node (ref "X6") (pin "1") (pinfunction "1_1") (pintype "passive"))
    )
    (net (code "32") (name "/INT") (class "Default")
      (node (ref "DA3") (pin "12") (pinfunction "INT_12") (pintype "passive"))
    )
    (net (code "33") (name "/Line1") (class "Default")
      (node (ref "X8") (pin "1") (pinfunction "1_1") (pintype "passive"))
    )
    (net (code "34") (name "/Line2") (class "Default")
      (node (ref "X7") (pin "1") (pinfunction "1_1") (pintype "passive"))
    )
    (net (code "35") (name "/MIC+") (class "Default")
      (node (ref "C22") (pin "1") (pinfunction "1_1") (pintype "passive"))
      (node (ref "R15") (pin "1") (pinfunction "1_1") (pintype "passive"))
    )
    (net (code "36") (name "/MIC-") (class "Default")
      (node (ref "C20") (pin "1") (pinfunction "1_1") (pintype "passive"))
      (node (ref "R16") (pin "1") (pinfunction "1_1") (pintype "passive"))
    )
    (net (code "37") (name "/OSC32IN") (class "Default")
      (node (ref "C5") (pin "2") (pinfunction "2_2") (pintype "passive"))
      (node (ref "R2") (pin "2") (pinfunction "2_2") (pintype "passive"))
      (node (ref "U1") (pin "3") (pinfunction "PC14-OSC32_IN_3") (pintype "bidirectional"))
      (node (ref "ZQ2") (pin "2") (pinfunction "2_2") (pintype "passive"))
    )
    (net (code "38") (name "/OSC32OUT") (class "Default")
      (node (ref "C2") (pin "2") (pinfunction "2_2") (pintype "passive"))
      (node (ref "R2") (pin "1") (pinfunction "1_1") (pintype "passive"))
      (node (ref "U1") (pin "4") (pinfunction "PC15-OSC32_OUT_4") (pintype "bidirectional"))
      (node (ref "ZQ2") (pin "1") (pinfunction "1_1") (pintype "passive"))
    )
    (net (code "39") (name "/OSCIN") (class "Default")
      (node (ref "C6") (pin "2") (pinfunction "2_2") (pintype "passive"))
      (node (ref "R1") (pin "1") (pinfunction "1_1") (pintype "passive"))
      (node (ref "U1") (pin "5") (pinfunction "OSC_IN/PF0_5") (pintype "input"))
      (node (ref "ZQ1") (pin "2") (pinfunction "2_2") (pintype "passive"))
    )
    (net (code "40") (name "/OSCOUT") (class "Default")
      (node (ref "C1") (pin "2") (pinfunction "2_2") (pintype "passive"))
      (node (ref "R1") (pin "2") (pinfunction "2_2") (pintype "passive"))
      (node (ref "U1") (pin "6") (pinfunction "OSC_OUT/PF1_6") (pintype "output"))
      (node (ref "ZQ1") (pin "1") (pinfunction "1_1") (pintype "passive"))
    )
    (net (code "41") (name "/OUTB") (class "Default")
      (node (ref "C21") (pin "1") (pinfunction "1_1") (pintype "passive"))
      (node (ref "D3") (pin "1") (pinfunction "1OUT_1") (pintype "passive"))
      (node (ref "R19") (pin "2") (pinfunction "2_2") (pintype "passive"))
      (node (ref "R61") (pin "2") (pinfunction "2_2") (pintype "passive"))
    )
    (net (code "42") (name "/OUTMIC") (class "Default")
      (node (ref "R61") (pin "1") (pinfunction "1_1") (pintype "passive"))
      (node (ref "U1") (pin "25") (pinfunction "PC5_25") (pintype "bidirectional"))
    )
    (net (code "43") (name "/RESET") (class "Default")
      (node (ref "C11") (pin "1") (pinfunction "1_1") (pintype "passive"))
      (node (ref "U1") (pin "7") (pinfunction "NRST_7") (pintype "bidirectional"))
      (node (ref "XT8") (pin "3") (pinfunction "3_3") (pintype "passive"))
    )
    (net (code "44") (name "/RST") (class "Default")
      (node (ref "H1") (pin "14") (pinfunction "RES#_14") (pintype "passive"))
      (node (ref "R53") (pin "2") (pinfunction "2_2") (pintype "passive"))
    )
    (net (code "45") (name "/RST_O") (class "Default")
      (node (ref "R53") (pin "1") (pinfunction "1_1") (pintype "passive"))
      (node (ref "U1") (pin "20") (pinfunction "PA4_20") (pintype "bidirectional"))
    )
    (net (code "46") (name "/RTS") (class "Default")
      (node (ref "D5") (pin "2") (pinfunction "~{RE}_2") (pintype "passive"))
      (node (ref "D5") (pin "3") (pinfunction "DE_3") (pintype "passive"))
      (node (ref "R63") (pin "1") (pinfunction "1_1") (pintype "passive"))
    )
    (net (code "47") (name "/RXD") (class "Default")
      (node (ref "D5") (pin "1") (pinfunction "RO_1") (pintype "passive"))
      (node (ref "R62") (pin "1") (pinfunction "1_1") (pintype "passive"))
    )
    (net (code "48") (name "/RXDO") (class "Default")
      (node (ref "U1") (pin "17") (pinfunction "PA3_17") (pintype "bidirectional"))
      (node (ref "XT7") (pin "2") (pinfunction "2_2") (pintype "passive"))
    )
    (net (code "49") (name "/SA0") (class "Default")
      (node (ref "H1") (pin "15") (pinfunction "D/C#_15") (pintype "passive"))
      (node (ref "R54") (pin "2") (pinfunction "2_2") (pintype "passive"))
      (node (ref "R60") (pin "2") (pinfunction "2_2") (pintype "passive"))
    )
    (net (code "50") (name "/SA0_O") (class "Default")
      (node (ref "R54") (pin "1") (pinfunction "1_1") (pintype "passive"))
      (node (ref "U1") (pin "22") (pinfunction "PA6_22") (pintype "bidirectional"))
    )
    (net (code "51") (name "/SCL1_O") (class "Default")
      (node (ref "R44") (pin "1") (pinfunction "1_1") (pintype "passive"))
      (node (ref "R57") (pin "1") (pinfunction "1_1") (pintype "passive"))
      (node (ref "U1") (pin "58") (pinfunction "PB6_58") (pintype "bidirectional"))
    )
    (net (code "52") (name "/SCL2_O") (class "Default")
      (node (ref "R31") (pin "1") (pinfunction "1_1") (pintype "passive"))
      (node (ref "R48") (pin "2") (pinfunction "2_2") (pintype "passive"))
      (node (ref "R49") (pin "2") (pinfunction "2_2") (pintype "passive"))
      (node (ref "U1") (pin "29") (pinfunction "PB10_29") (pintype "bidirectional"))
      (node (ref "XT1") (pin "3") (pinfunction "3_3") (pintype "passive"))
    )
    (net (code "53") (name "/SDA1_O") (class "Default")
      (node (ref "R45") (pin "1") (pinfunction "1_1") (pintype "passive"))
      (node (ref "R58") (pin "1") (pinfunction "1_1") (pintype "passive"))
      (node (ref "U1") (pin "59") (pinfunction "PB7_59") (pintype "bidirectional"))
    )
    (net (code "54") (name "/SDA2_O") (class "Default")
      (node (ref "R32") (pin "1") (pinfunction "1_1") (pintype "passive"))
      (node (ref "R47") (pin "2") (pinfunction "2_2") (pintype "passive"))
      (node (ref "R50") (pin "2") (pinfunction "2_2") (pintype "passive"))
      (node (ref "U1") (pin "30") (pinfunction "PB11_30") (pintype "bidirectional"))
      (node (ref "XT1") (pin "2") (pinfunction "2_2") (pintype "passive"))
    )
    (net (code "55") (name "/SPI1_MOSI") (class "Default")
      (node (ref "R56") (pin "1") (pinfunction "1_1") (pintype "passive"))
      (node (ref "U1") (pin "23") (pinfunction "PA7_23") (pintype "bidirectional"))
    )
    (net (code "56") (name "/SPI1_SCK") (class "Default")
      (node (ref "R55") (pin "1") (pinfunction "1_1") (pintype "passive"))
      (node (ref "U1") (pin "21") (pinfunction "PA5_21") (pintype "bidirectional"))
    )
    (net (code "57") (name "/SPI2_MISO") (class "Default")
      (node (ref "U1") (pin "10") (pinfunction "PC2_10") (pintype "bidirectional"))
      (node (ref "XT2") (pin "1") (pinfunction "1_1") (pintype "passive"))
    )
    (net (code "58") (name "/SPI2_MOSI") (class "Default")
      (node (ref "U1") (pin "11") (pinfunction "PC3_11") (pintype "bidirectional"))
      (node (ref "XT2") (pin "2") (pinfunction "2_2") (pintype "passive"))
    )
    (net (code "59") (name "/SPI2_RST") (class "Default")
      (node (ref "U1") (pin "9") (pinfunction "PC1_9") (pintype "bidirectional"))
      (node (ref "XT2") (pin "4") (pinfunction "4_4") (pintype "passive"))
    )
    (net (code "60") (name "/SPI2_SCK") (class "Default")
      (node (ref "U1") (pin "34") (pinfunction "PB13_34") (pintype "bidirectional"))
      (node (ref "XT2") (pin "3") (pinfunction "3_3") (pintype "passive"))
    )
    (net (code "61") (name "/ST1") (class "Default")
      (node (ref "R3") (pin "2") (pinfunction "2_2") (pintype "passive"))
      (node (ref "U1") (pin "36") (pinfunction "PB15_36") (pintype "bidirectional"))
    )
    (net (code "62") (name "/ST2") (class "Default")
      (node (ref "R4") (pin "2") (pinfunction "2_2") (pintype "passive"))
      (node (ref "U1") (pin "35") (pinfunction "PB14_35") (pintype "bidirectional"))
    )
    (net (code "63") (name "/STAT") (class "Default")
      (node (ref "D2") (pin "1") (pinfunction "Stat_1") (pintype "power_in"))
      (node (ref "HL2") (pin "2") (pinfunction "C_2") (pintype "passive"))
      (node (ref "R14") (pin "1") (pinfunction "1_1") (pintype "passive"))
    )
    (net (code "64") (name "/SWCLK") (class "Default")
      (node (ref "U1") (pin "49") (pinfunction "PA14/JTCK/SWCLK_49") (pintype "bidirectional"))
      (node (ref "XT8") (pin "2") (pinfunction "2_2") (pintype "passive"))
    )
    (net (code "65") (name "/SWDIO") (class "Default")
      (node (ref "U1") (pin "46") (pinfunction "PA13/JTMS/SWDIO_46") (pintype "bidirectional"))
      (node (ref "XT8") (pin "1") (pinfunction "1_1") (pintype "passive"))
    )
    (net (code "66") (name "/TIM3_CH1") (class "Default")
      (node (ref "R65") (pin "2") (pinfunction "2_2") (pintype "passive"))
      (node (ref "U1") (pin "37") (pinfunction "PC6_37") (pintype "bidirectional"))
    )
    (net (code "67") (name "/TMP") (class "Default")
      (node (ref "D6") (pin "2") (pinfunction "Vo_2") (pintype "passive"))
      (node (ref "U1") (pin "8") (pinfunction "PC0_8") (pintype "bidirectional"))
    )
    (net (code "68") (name "/TXD") (class "Default")
      (node (ref "D5") (pin "4") (pinfunction "DI_4") (pintype "passive"))
      (node (ref "R64") (pin "1") (pinfunction "1_1") (pintype "passive"))
    )
    (net (code "69") (name "/TXDO") (class "Default")
      (node (ref "U1") (pin "16") (pinfunction "PA2_16") (pintype "bidirectional"))
      (node (ref "XT7") (pin "3") (pinfunction "3_3") (pintype "passive"))
    )
    (net (code "70") (name "/USART1_RTS") (class "Default")
      (node (ref "R63") (pin "2") (pinfunction "2_2") (pintype "passive"))
      (node (ref "U1") (pin "41") (pinfunction "PA8_41") (pintype "bidirectional"))
    )
    (net (code "71") (name "/USART1_RX") (class "Default")
      (node (ref "R62") (pin "2") (pinfunction "2_2") (pintype "passive"))
      (node (ref "U1") (pin "43") (pinfunction "PA10_43") (pintype "bidirectional"))
    )
    (net (code "72") (name "/USART1_TX") (class "Default")
      (node (ref "R64") (pin "2") (pinfunction "2_2") (pintype "passive"))
      (node (ref "U1") (pin "42") (pinfunction "PA9_42") (pintype "bidirectional"))
    )
    (net (code "73") (name "/VIBRO") (class "Default")
      (node (ref "R59") (pin "1") (pinfunction "1_1") (pintype "passive"))
      (node (ref "U1") (pin "28") (pinfunction "PB2_28") (pintype "bidirectional"))
      (node (ref "VT2") (pin "1") (pinfunction "B_1") (pintype "passive"))
    )
    (net (code "74") (name "/ZUM") (class "Default")
      (node (ref "R6") (pin "2") (pinfunction "2_2") (pintype "passive"))
      (node (ref "U1") (pin "62") (pinfunction "PB9_62") (pintype "bidirectional"))
      (node (ref "VT1") (pin "1") (pinfunction "B_1") (pintype "passive"))
    )
    (net (code "75") (name "3V3") (class "Default")
      (node (ref "B1") (pin "1") (pinfunction "+_1") (pintype "passive"))
      (node (ref "C10") (pin "1") (pinfunction "1_1") (pintype "passive"))
      (node (ref "C23") (pin "2") (pinfunction "2_2") (pintype "passive"))
      (node (ref "C24") (pin "2") (pinfunction "2_2") (pintype "passive"))
      (node (ref "C3") (pin "1") (pinfunction "1_1") (pintype "passive"))
      (node (ref "C32") (pin "1") (pinfunction "1_1") (pintype "passive"))
      (node (ref "C33") (pin "2") (pinfunction "2_2") (pintype "passive"))
      (node (ref "C34") (pin "2") (pinfunction "2_2") (pintype "passive"))
      (node (ref "C36") (pin "1") (pinfunction "1_1") (pintype "passive"))
      (node (ref "C38") (pin "2") (pinfunction "2_2") (pintype "passive"))
      (node (ref "C39") (pin "1") (pinfunction "1_1") (pintype "passive"))
      (node (ref "C4") (pin "1") (pinfunction "1_1") (pintype "passive"))
      (node (ref "C40") (pin "1") (pinfunction "1_1") (pintype "passive"))
      (node (ref "C49") (pin "1") (pinfunction "1_1") (pintype "passive"))
      (node (ref "C51") (pin "1") (pinfunction "1_1") (pintype "passive"))
      (node (ref "C52") (pin "1") (pinfunction "1_1") (pintype "passive"))
      (node (ref "C7") (pin "1") (pinfunction "1_1") (pintype "passive"))
      (node (ref "C8") (pin "1") (pinfunction "1_1") (pintype "passive"))
      (node (ref "D3") (pin "8") (pinfunction "Vcc_8") (pintype "passive"))
      (node (ref "D4") (pin "2") (pinfunction "OUT_2") (pintype "passive"))
      (node (ref "D4") (pin "4") (pinfunction "OUT_4") (pintype "passive"))
      (node (ref "D5") (pin "8") (pinfunction "VCC_8") (pintype "passive"))
      (node (ref "D7") (pin "5") (pinfunction "Vdd_5") (pintype "passive"))
      (node (ref "DA1") (pin "1") (pinfunction "VDD_1") (pintype "passive"))
      (node (ref "DA2") (pin "1") (pinfunction "AVDD_1") (pintype "passive"))
      (node (ref "DA2") (pin "11") (pinfunction "AVDD_11") (pintype "passive"))
      (node (ref "DA3") (pin "13") (pinfunction "VDD_13") (pintype "passive"))
      (node (ref "DA3") (pin "8") (pinfunction "VLOGIC_8") (pintype "passive"))
      (node (ref "H1") (pin "6") (pinfunction "VBAT_6") (pintype "passive"))
      (node (ref "H1") (pin "9") (pinfunction "VDD_9") (pintype "passive"))
      (node (ref "HL1") (pin "1") (pinfunction "A_1") (pintype "passive"))
      (node (ref "HL1") (pin "3") (pinfunction "A_3") (pintype "passive"))
      (node (ref "J1") (pin "1") (pinfunction "1_1") (pintype "passive"))
      (node (ref "J2") (pin "1") (pinfunction "1_1") (pintype "passive"))
      (node (ref "J3") (pin "1") (pinfunction "1_1") (pintype "passive"))
      (node (ref "M1") (pin "1") (pinfunction "P_1") (pintype "passive"))
      (node (ref "R27") (pin "2") (pinfunction "2_2") (pintype "passive"))
      (node (ref "R28") (pin "2") (pinfunction "2_2") (pintype "passive"))
      (node (ref "R29") (pin "2") (pinfunction "2_2") (pintype "passive"))
      (node (ref "R31") (pin "2") (pinfunction "2_2") (pintype "passive"))
      (node (ref "R32") (pin "2") (pinfunction "2_2") (pintype "passive"))
      (node (ref "R33") (pin "2") (pinfunction "2_2") (pintype "passive"))
      (node (ref "R35") (pin "2") (pinfunction "2_2") (pintype "passive"))
      (node (ref "R44") (pin "2") (pinfunction "2_2") (pintype "passive"))
      (node (ref "R45") (pin "2") (pinfunction "2_2") (pintype "passive"))
      (node (ref "R66") (pin "1") (pinfunction "1_1") (pintype "passive"))
      (node (ref "R67") (pin "1") (pinfunction "1_1") (pintype "passive"))
      (node (ref "U1") (pin "13") (pinfunction "VDDA_13") (pintype "power_in"))
      (node (ref "U1") (pin "19") (pinfunction "VDD_4_19") (pintype "power_in"))
      (node (ref "U1") (pin "32") (pinfunction "VDD_1_32") (pintype "power_in"))
      (node (ref "U1") (pin "48") (pinfunction "VDD_2_48") (pintype "power_in"))
      (node (ref "U1") (pin "64") (pinfunction "VDD_3_64") (pintype "power_in"))
      (node (ref "VD3") (pin "1") (pinfunction "K_1") (pintype "passive"))
    )
    (net (code "76") (name "5V") (class "Default")
      (node (ref "C26") (pin "2") (pinfunction "2_2") (pintype "passive"))
      (node (ref "C30") (pin "2") (pinfunction "2_2") (pintype "passive"))
      (node (ref "C44") (pin "1") (pinfunction "1_1") (pintype "passive"))
      (node (ref "C45") (pin "2") (pinfunction "2_2") (pintype "passive"))
      (node (ref "C46") (pin "2") (pinfunction "2_2") (pintype "passive"))
      (node (ref "C47") (pin "2") (pinfunction "2_2") (pintype "passive"))
      (node (ref "D4") (pin "3") (pinfunction "IN_3") (pintype "passive"))
      (node (ref "D6") (pin "1") (pinfunction "Vs_1") (pintype "passive"))
      (node (ref "HL3") (pin "1") (pinfunction "Vdd_1") (pintype "passive"))
      (node (ref "HL4") (pin "1") (pinfunction "Vdd_1") (pintype "passive"))
      (node (ref "HL5") (pin "1") (pinfunction "Vdd_1") (pintype "passive"))
      (node (ref "R22") (pin "1") (pinfunction "1_1") (pintype "passive"))
      (node (ref "U2") (pin "1") (pinfunction "VDD_1") (pintype "power_in"))
      (node (ref "VD1") (pin "1") (pinfunction "K_1") (pintype "passive"))
    )
    (net (code "77") (name "GND") (class "Default")
      (node (ref "BT1") (pin "2") (pinfunction "-_2") (pintype "passive"))
      (node (ref "C1") (pin "1") (pinfunction "1_1") (pintype "passive"))
      (node (ref "C10") (pin "2") (pinfunction "2_2") (pintype "passive"))
      (node (ref "C11") (pin "2") (pinfunction "2_2") (pintype "passive"))
      (node (ref "C12") (pin "1") (pinfunction "1_1") (pintype "passive"))
      (node (ref "C13") (pin "2") (pinfunction "2_2") (pintype "passive"))
      (node (ref "C14") (pin "2") (pinfunction "2_2") (pintype "passive"))
      (node (ref "C15") (pin "1") (pinfunction "1_1") (pintype "passive"))
      (node (ref "C16") (pin "1") (pinfunction "1_1") (pintype "passive"))
      (node (ref "C17") (pin "1") (pinfunction "1_1") (pintype "passive"))
      (node (ref "C18") (pin "1") (pinfunction "1_1") (pintype "passive"))
      (node (ref "C19") (pin "1") (pinfunction "1_1") (pintype "passive"))
      (node (ref "C2") (pin "1") (pinfunction "1_1") (pintype "passive"))
      (node (ref "C23") (pin "1") (pinfunction "1_1") (pintype "passive"))
      (node (ref "C24") (pin "1") (pinfunction "1_1") (pintype "passive"))
      (node (ref "C25") (pin "1") (pinfunction "1_1") (pintype "passive"))
      (node (ref "C26") (pin "1") (pinfunction "1_1") (pintype "passive"))
      (node (ref "C27") (pin "2") (pinfunction "2_2") (pintype "passive"))
      (node (ref "C28") (pin "2") (pinfunction "2_2") (pintype "passive"))
      (node (ref "C29") (pin "1") (pinfunction "1_1") (pintype "passive"))
      (node (ref "C3") (pin "2") (pinfunction "2_2") (pintype "passive"))
      (node (ref "C30") (pin "1") (pinfunction "1_1") (pintype "passive"))
      (node (ref "C31") (pin "1") (pinfunction "1_1") (pintype "passive"))
      (node (ref "C32") (pin "2") (pinfunction "2_2") (pintype "passive"))
      (node (ref "C33") (pin "1") (pinfunction "1_1") (pintype "passive"))
      (node (ref "C34") (pin "1") (pinfunction "1_1") (pintype "passive"))
      (node (ref "C35") (pin "1") (pinfunction "1_1") (pintype "passive"))
      (node (ref "C36") (pin "2") (pinfunction "2_2") (pintype "passive"))
      (node (ref "C37") (pin "1") (pinfunction "1_1") (pintype "passive"))
      (node (ref "C38") (pin "1") (pinfunction "1_1") (pintype "passive"))
      (node (ref "C39") (pin "2") (pinfunction "2_2") (pintype "passive"))
      (node (ref "C4") (pin "2") (pinfunction "2_2") (pintype "passive"))
      (node (ref "C40") (pin "2") (pinfunction "2_2") (pintype "passive"))
      (node (ref "C41") (pin "2") (pinfunction "2_2") (pintype "passive"))
      (node (ref "C42") (pin "1") (pinfunction "1_1") (pintype "passive"))
      (node (ref "C44") (pin "2") (pinfunction "2_2") (pintype "passive"))
      (node (ref "C45") (pin "1") (pinfunction "1_1") (pintype "passive"))
      (node (ref "C46") (pin "1") (pinfunction "1_1") (pintype "passive"))
      (node (ref "C47") (pin "1") (pinfunction "1_1") (pintype "passive"))
      (node (ref "C49") (pin "2") (pinfunction "2_2") (pintype "passive"))
      (node (ref "C5") (pin "1") (pinfunction "1_1") (pintype "passive"))
      (node (ref "C51") (pin "2") (pinfunction "2_2") (pintype "passive"))
      (node (ref "C52") (pin "2") (pinfunction "2_2") (pintype "passive"))
      (node (ref "C53") (pin "2") (pinfunction "2_2") (pintype "passive"))
      (node (ref "C54") (pin "2") (pinfunction "2_2") (pintype "passive"))
      (node (ref "C55") (pin "1") (pinfunction "1_1") (pintype "passive"))
      (node (ref "C6") (pin "1") (pinfunction "1_1") (pintype "passive"))
      (node (ref "C7") (pin "2") (pinfunction "2_2") (pintype "passive"))
      (node (ref "C8") (pin "2") (pinfunction "2_2") (pintype "passive"))
      (node (ref "C9") (pin "2") (pinfunction "2_2") (pintype "passive"))
      (node (ref "D1") (pin "0") (pinfunction "body_0") (pintype "passive"))
      (node (ref "D1") (pin "5") (pinfunction "GND_5") (pintype "passive"))
      (node (ref "D2") (pin "2") (pinfunction "Vss_2") (pintype "power_in"))
      (node (ref "D3") (pin "0") (pinfunction "PP_0") (pintype "passive"))
      (node (ref "D3") (pin "4") (pinfunction "GND_4") (pintype "passive"))
      (node (ref "D4") (pin "1") (pinfunction "GND_1") (pintype "passive"))
      (node (ref "D5") (pin "0") (pinfunction "EP_0") (pintype "passive"))
      (node (ref "D5") (pin "5") (pinfunction "GND_5") (pintype "passive"))
      (node (ref "D6") (pin "3") (pinfunction "GND_3") (pintype "passive"))
      (node (ref "D7") (pin "2") (pinfunction "Vss_2") (pintype "passive"))
      (node (ref "DA1") (pin "4") (pinfunction "GND_4") (pintype "passive"))
      (node (ref "DA2") (pin "12") (pinfunction "GND4_12") (pintype "passive"))
      (node (ref "DA2") (pin "2") (pinfunction "AVSS_2") (pintype "passive"))
      (node (ref "DA2") (pin "3") (pinfunction "GND_3") (pintype "passive"))
      (node (ref "DA2") (pin "4") (pinfunction "GND2_4") (pintype "passive"))
      (node (ref "DA2") (pin "6") (pinfunction "GND3_6") (pintype "passive"))
      (node (ref "DA3") (pin "1") (pinfunction "CLKIN_1") (pintype "passive"))
      (node (ref "DA3") (pin "11") (pinfunction "FSYNC_11") (pintype "passive"))
      (node (ref "DA3") (pin "18") (pinfunction "GND_18") (pintype "passive"))
      (node (ref "DA3") (pin "9") (pinfunction "AD0_9") (pintype "passive"))
      (node (ref "H1") (pin "1") (pinfunction "NC(GND)_1") (pintype "passive"))
      (node (ref "H1") (pin "12") (pinfunction "BS2_12") (pintype "passive"))
      (node (ref "H1") (pin "29") (pinfunction "VLSS_29") (pintype "passive"))
      (node (ref "H1") (pin "30") (pinfunction "NC(GND)_30") (pintype "passive"))
      (node (ref "H1") (pin "8") (pinfunction "VSS_8") (pintype "passive"))
      (node (ref "HL2") (pin "4") (pinfunction "C_4") (pintype "passive"))
      (node (ref "HL3") (pin "3") (pinfunction "Vss_3") (pintype "passive"))
      (node (ref "HL4") (pin "3") (pinfunction "Vss_3") (pintype "passive"))
      (node (ref "HL5") (pin "3") (pinfunction "Vss_3") (pintype "passive"))
      (node (ref "J2") (pin "3") (pinfunction "3_3") (pintype "passive"))
      (node (ref "J3") (pin "3") (pinfunction "3_3") (pintype "passive"))
      (node (ref "R11") (pin "2") (pinfunction "2_2") (pintype "passive"))
      (node (ref "R18") (pin "2") (pinfunction "2_2") (pintype "passive"))
      (node (ref "R20") (pin "2") (pinfunction "2_2") (pintype "passive"))
      (node (ref "R23") (pin "2") (pinfunction "2_2") (pintype "passive"))
      (node (ref "R24") (pin "1") (pinfunction "1_1") (pintype "passive"))
      (node (ref "R26") (pin "1") (pinfunction "1_1") (pintype "passive"))
      (node (ref "R36") (pin "2") (pinfunction "2_2") (pintype "passive"))
      (node (ref "R37") (pin "2") (pinfunction "2_2") (pintype "passive"))
      (node (ref "R38") (pin "2") (pinfunction "2_2") (pintype "passive"))
      (node (ref "R43") (pin "1") (pinfunction "1_1") (pintype "passive"))
      (node (ref "R5") (pin "2") (pinfunction "2_2") (pintype "passive"))
      (node (ref "R59") (pin "2") (pinfunction "2_2") (pintype "passive"))
      (node (ref "R6") (pin "1") (pinfunction "1_1") (pintype "passive"))
      (node (ref "R60") (pin "1") (pinfunction "1_1") (pintype "passive"))
      (node (ref "R8") (pin "2") (pinfunction "2_2") (pintype "passive"))
      (node (ref "SW1") (pin "1") (pinfunction "1_1") (pintype "passive"))
      (node (ref "SW2") (pin "1") (pinfunction "1_1") (pintype "passive"))
      (node (ref "SW3") (pin "1") (pinfunction "1_1") (pintype "passive"))
      (node (ref "SW4") (pin "1") (pinfunction "1_1") (pintype "passive"))
      (node (ref "SW5") (pin "1") (pinfunction "1_1") (pintype "passive"))
      (node (ref "SW6") (pin "1") (pinfunction "1_1") (pintype "passive"))
      (node (ref "SW7") (pin "1") (pinfunction "1_1") (pintype "passive"))
      (node (ref "SW8") (pin "1") (pinfunction "1_1") (pintype "passive"))
      (node (ref "SW9") (pin "2") (pinfunction "2_2") (pintype "passive"))
      (node (ref "U1") (pin "12") (pinfunction "VSSA_12") (pintype "power_in"))
      (node (ref "U1") (pin "18") (pinfunction "VSS_4_18") (pintype "power_in"))
      (node (ref "U1") (pin "63") (pinfunction "VSS_3_63") (pintype "power_in"))
      (node (ref "U2") (pin "4") (pinfunction "GND_4") (pintype "power_in"))
      (node (ref "U2") (pin "5") (pinfunction "IN-_5") (pintype "power_in"))
      (node (ref "VD2") (pin "2") (pinfunction "GND_2") (pintype "power_in"))
      (node (ref "VT1") (pin "2") (pinfunction "E_2") (pintype "passive"))
      (node (ref "VT2") (pin "2") (pinfunction "E_2") (pintype "passive"))
      (node (ref "XT1") (pin "0") (pinfunction "0_0") (pintype "passive"))
      (node (ref "XT1") (pin "4") (pinfunction "4_4") (pintype "passive"))
      (node (ref "XT2") (pin "0") (pinfunction "0_0") (pintype "passive"))
      (node (ref "XT3") (pin "0") (pinfunction "0_0") (pintype "passive"))
      (node (ref "XT3") (pin "4") (pinfunction "4_4") (pintype "passive"))
      (node (ref "XT4") (pin "2") (pinfunction "GND_2") (pintype "passive"))
      (node (ref "XT6") (pin "0") (pinfunction "0_0") (pintype "passive"))
      (node (ref "XT6") (pin "4") (pinfunction "4_4") (pintype "passive"))
      (node (ref "XT7") (pin "0") (pinfunction "0_0") (pintype "passive"))
      (node (ref "XT7") (pin "4") (pinfunction "4_4") (pintype "passive"))
      (node (ref "XT8") (pin "0") (pinfunction "0_0") (pintype "passive"))
      (node (ref "XT8") (pin "4") (pinfunction "4_4") (pintype "passive"))
    )
    (net (code "78") (name "GNDA") (class "Default")
      (node (ref "C27") (pin "1") (pinfunction "1_1") (pintype "passive"))
      (node (ref "C28") (pin "1") (pinfunction "1_1") (pintype "passive"))
      (node (ref "D3") (pin "5") (pinfunction "2IN+_5") (pintype "passive"))
      (node (ref "D3") (pin "6") (pinfunction "2IN-_6") (pintype "passive"))
      (node (ref "R17") (pin "1") (pinfunction "1_1") (pintype "passive"))
      (node (ref "R26") (pin "2") (pinfunction "2_2") (pintype "passive"))
      (node (ref "R28") (pin "1") (pinfunction "1_1") (pintype "passive"))
    )
    (net (code "79") (name "Net-(D2-Prog)") (class "Default")
      (node (ref "D2") (pin "5") (pinfunction "Prog_5") (pintype "power_in"))
      (node (ref "R24") (pin "2") (pinfunction "2_2") (pintype "passive"))
    )
    (net (code "80") (name "Net-(D3A-1IN+)") (class "Default")
      (node (ref "D3") (pin "3") (pinfunction "1IN+_3") (pintype "passive"))
      (node (ref "R15") (pin "2") (pinfunction "2_2") (pintype "passive"))
      (node (ref "R17") (pin "2") (pinfunction "2_2") (pintype "passive"))
    )
    (net (code "81") (name "Net-(D3A-1IN-)") (class "Default")
      (node (ref "C21") (pin "2") (pinfunction "2_2") (pintype "passive"))
      (node (ref "D3") (pin "2") (pinfunction "1IN-_2") (pintype "passive"))
      (node (ref "R16") (pin "2") (pinfunction "2_2") (pintype "passive"))
      (node (ref "R19") (pin "1") (pinfunction "1_1") (pintype "passive"))
    )
    (net (code "82") (name "Net-(D7-IN-)") (class "Default")
      (node (ref "C43") (pin "2") (pinfunction "2_2") (pintype "passive"))
      (node (ref "D7") (pin "4") (pinfunction "IN-_4") (pintype "passive"))
      (node (ref "R38") (pin "1") (pinfunction "1_1") (pintype "passive"))
      (node (ref "R40") (pin "2") (pinfunction "2_2") (pintype "passive"))
    )
    (net (code "83") (name "Net-(DA1-OUT+)") (class "Default")
      (node (ref "C22") (pin "2") (pinfunction "2_2") (pintype "passive"))
      (node (ref "DA1") (pin "3") (pinfunction "OUT+_3") (pintype "passive"))
      (node (ref "R20") (pin "1") (pinfunction "1_1") (pintype "passive"))
    )
    (net (code "84") (name "Net-(DA1-OUT-)") (class "Default")
      (node (ref "C20") (pin "2") (pinfunction "2_2") (pintype "passive"))
      (node (ref "DA1") (pin "2") (pinfunction "OUT-_2") (pintype "passive"))
      (node (ref "R18") (pin "1") (pinfunction "1_1") (pintype "passive"))
    )
    (net (code "85") (name "Net-(DA2-GPIO1)") (class "Default")
      (node (ref "DA2") (pin "7") (pinfunction "GPIO1_7") (pintype "passive"))
      (node (ref "R29") (pin "1") (pinfunction "1_1") (pintype "passive"))
    )
    (net (code "86") (name "Net-(DA2-SCL)") (class "Default")
      (node (ref "DA2") (pin "10") (pinfunction "SCL_10") (pintype "passive"))
      (node (ref "R48") (pin "1") (pinfunction "1_1") (pintype "passive"))
    )
    (net (code "87") (name "Net-(DA2-SDA)") (class "Default")
      (node (ref "DA2") (pin "9") (pinfunction "SDA_9") (pintype "passive"))
      (node (ref "R47") (pin "1") (pinfunction "1_1") (pintype "passive"))
    )
    (net (code "88") (name "Net-(DA2-XSHUT)") (class "Default")
      (node (ref "DA2") (pin "5") (pinfunction "XSHUT_5") (pintype "passive"))
      (node (ref "R33") (pin "1") (pinfunction "1_1") (pintype "passive"))
    )
    (net (code "89") (name "Net-(DA3-CPOUT)") (class "Default")
      (node (ref "C41") (pin "1") (pinfunction "1_1") (pintype "passive"))
      (node (ref "DA3") (pin "20") (pinfunction "CPOUT_20") (pintype "passive"))
    )
    (net (code "90") (name "Net-(DA3-REGOUT)") (class "Default")
      (node (ref "C35") (pin "2") (pinfunction "2_2") (pintype "passive"))
      (node (ref "DA3") (pin "10") (pinfunction "REGOUT_10") (pintype "passive"))
    )
    (net (code "91") (name "Net-(DA3-SCL)") (class "Default")
      (node (ref "DA3") (pin "23") (pinfunction "SCL_23") (pintype "passive"))
      (node (ref "R49") (pin "1") (pinfunction "1_1") (pintype "passive"))
    )
    (net (code "92") (name "Net-(DA3-SDA)") (class "Default")
      (node (ref "DA3") (pin "24") (pinfunction "SDA_24") (pintype "passive"))
      (node (ref "R50") (pin "1") (pinfunction "1_1") (pintype "passive"))
    )
    (net (code "93") (name "Net-(H1-C1N)") (class "Default")
      (node (ref "C50") (pin "2") (pinfunction "2_2") (pintype "passive"))
      (node (ref "H1") (pin "5") (pinfunction "C1N_5") (pintype "passive"))
    )
    (net (code "94") (name "Net-(H1-C1P)") (class "Default")
      (node (ref "C50") (pin "1") (pinfunction "1_1") (pintype "passive"))
      (node (ref "H1") (pin "4") (pinfunction "C1P_4") (pintype "passive"))
    )
    (net (code "95") (name "Net-(H1-C2N)") (class "Default")
      (node (ref "C48") (pin "2") (pinfunction "2_2") (pintype "passive"))
      (node (ref "H1") (pin "3") (pinfunction "C2N_3") (pintype "passive"))
    )
    (net (code "96") (name "Net-(H1-C2P)") (class "Default")
      (node (ref "C48") (pin "1") (pinfunction "1_1") (pintype "passive"))
      (node (ref "H1") (pin "2") (pinfunction "C2P_2") (pintype "passive"))
    )
    (net (code "97") (name "Net-(H1-D2)") (class "Default")
      (node (ref "H1") (pin "20") (pinfunction "D2_20") (pintype "passive"))
      (node (ref "R46") (pin "2") (pinfunction "2_2") (pintype "passive"))
    )
    (net (code "98") (name "Net-(H1-IREF)") (class "Default")
      (node (ref "H1") (pin "26") (pinfunction "IREF_26") (pintype "passive"))
      (node (ref "R43") (pin "2") (pinfunction "2_2") (pintype "passive"))
    )
    (net (code "99") (name "Net-(H1-VCC)") (class "Default")
      (node (ref "C54") (pin "1") (pinfunction "1_1") (pintype "passive"))
      (node (ref "H1") (pin "28") (pinfunction "VCC_28") (pintype "passive"))
    )
    (net (code "100") (name "Net-(H1-VCOMH)") (class "Default")
      (node (ref "C53") (pin "1") (pinfunction "1_1") (pintype "passive"))
      (node (ref "H1") (pin "27") (pinfunction "VCOMH_27") (pintype "passive"))
    )
    (net (code "101") (name "Net-(HL1-C-Pad2)") (class "Default")
      (node (ref "HL1") (pin "2") (pinfunction "C_2") (pintype "passive"))
      (node (ref "R3") (pin "1") (pinfunction "1_1") (pintype "passive"))
    )
    (net (code "102") (name "Net-(HL1-C-Pad4)") (class "Default")
      (node (ref "HL1") (pin "4") (pinfunction "C_4") (pintype "passive"))
      (node (ref "R4") (pin "1") (pinfunction "1_1") (pintype "passive"))
    )
    (net (code "103") (name "Net-(HL2-A-Pad1)") (class "Default")
      (node (ref "HL2") (pin "1") (pinfunction "A_1") (pintype "passive"))
      (node (ref "R13") (pin "2") (pinfunction "2_2") (pintype "passive"))
    )
    (net (code "104") (name "Net-(HL2-A-Pad3)") (class "Default")
      (node (ref "HL2") (pin "3") (pinfunction "A_3") (pintype "passive"))
      (node (ref "R14") (pin "2") (pinfunction "2_2") (pintype "passive"))
    )
    (net (code "105") (name "Net-(M1-N)") (class "Default")
      (node (ref "M1") (pin "2") (pinfunction "N_2") (pintype "passive"))
      (node (ref "R51") (pin "1") (pinfunction "1_1") (pintype "passive"))
    )
    (net (code "106") (name "Net-(R9-Pad2)") (class "Default")
      (node (ref "R9") (pin "2") (pinfunction "2_2") (pintype "passive"))
      (node (ref "SW1") (pin "2") (pinfunction "2_2") (pintype "passive"))
    )
    (net (code "107") (name "Net-(R12-Pad2)") (class "Default")
      (node (ref "R12") (pin "2") (pinfunction "2_2") (pintype "passive"))
      (node (ref "SW2") (pin "2") (pinfunction "2_2") (pintype "passive"))
    )
    (net (code "108") (name "Net-(R21-Pad2)") (class "Default")
      (node (ref "R21") (pin "2") (pinfunction "2_2") (pintype "passive"))
      (node (ref "SW3") (pin "2") (pinfunction "2_2") (pintype "passive"))
    )
    (net (code "109") (name "Net-(R25-Pad2)") (class "Default")
      (node (ref "R25") (pin "2") (pinfunction "2_2") (pintype "passive"))
      (node (ref "SW4") (pin "2") (pinfunction "2_2") (pintype "passive"))
    )
    (net (code "110") (name "Net-(R30-Pad2)") (class "Default")
      (node (ref "R30") (pin "2") (pinfunction "2_2") (pintype "passive"))
      (node (ref "SW5") (pin "2") (pinfunction "2_2") (pintype "passive"))
    )
    (net (code "111") (name "Net-(R34-Pad2)") (class "Default")
      (node (ref "R34") (pin "2") (pinfunction "2_2") (pintype "passive"))
      (node (ref "SW6") (pin "2") (pinfunction "2_2") (pintype "passive"))
    )
    (net (code "112") (name "Net-(R41-Pad2)") (class "Default")
      (node (ref "R41") (pin "2") (pinfunction "2_2") (pintype "passive"))
      (node (ref "SW7") (pin "2") (pinfunction "2_2") (pintype "passive"))
    )
    (net (code "113") (name "Net-(R42-Pad2)") (class "Default")
      (node (ref "R42") (pin "2") (pinfunction "2_2") (pintype "passive"))
      (node (ref "SW8") (pin "2") (pinfunction "2_2") (pintype "passive"))
    )
    (net (code "114") (name "Net-(U1-BOOT0)") (class "Default")
      (node (ref "R5") (pin "1") (pinfunction "1_1") (pintype "passive"))
      (node (ref "U1") (pin "60") (pinfunction "BOOT0_60") (pintype "input"))
    )
    (net (code "115") (name "Net-(U1-VSS_1)") (class "Default")
      (node (ref "C14") (pin "1") (pinfunction "1_1") (pintype "passive"))
      (node (ref "U1") (pin "31") (pinfunction "VSS_1_31") (pintype "power_in"))
    )
    (net (code "116") (name "Net-(U1-VSS_2)") (class "Default")
      (node (ref "C13") (pin "1") (pinfunction "1_1") (pintype "passive"))
      (node (ref "U1") (pin "47") (pinfunction "VSS_2_47") (pintype "power_in"))
    )
    (net (code "117") (name "Net-(U2-IN+)") (class "Default")
      (node (ref "R65") (pin "1") (pinfunction "1_1") (pintype "passive"))
      (node (ref "U2") (pin "6") (pinfunction "IN+_6") (pintype "power_in"))
    )
    (net (code "118") (name "Net-(VD1-A)") (class "Default")
      (node (ref "L1") (pin "2") (pinfunction "2_2") (pintype "passive"))
      (node (ref "VD1") (pin "2") (pinfunction "A_2") (pintype "passive"))
      (node (ref "XT4") (pin "1") (pinfunction "SW_1") (pintype "passive"))
    )
    (net (code "119") (name "Net-(VD3-A)") (class "Default")
      (node (ref "B1") (pin "2") (pinfunction "-_2") (pintype "passive"))
      (node (ref "B1") (pin "3") (pinfunction "-_3") (pintype "passive"))
      (node (ref "B1") (pin "4") (pinfunction "-_4") (pintype "passive"))
      (node (ref "VD3") (pin "2") (pinfunction "A_2") (pintype "passive"))
      (node (ref "VT1") (pin "3") (pinfunction "C_3") (pintype "passive"))
    )
    (net (code "120") (name "Net-(VD4-A)") (class "Default")
      (node (ref "R67") (pin "2") (pinfunction "2_2") (pintype "passive"))
      (node (ref "VD4") (pin "2") (pinfunction "A_2") (pintype "passive"))
    )
    (net (code "121") (name "Net-(VT2-C)") (class "Default")
      (node (ref "R51") (pin "2") (pinfunction "2_2") (pintype "passive"))
      (node (ref "VT2") (pin "3") (pinfunction "C_3") (pintype "passive"))
    )
    (net (code "122") (name "Net-(XT4-FB)") (class "Default")
      (node (ref "R22") (pin "2") (pinfunction "2_2") (pintype "passive"))
      (node (ref "R23") (pin "1") (pinfunction "1_1") (pintype "passive"))
      (node (ref "XT4") (pin "3") (pinfunction "FB_3") (pintype "passive"))
    )
    (net (code "123") (name "VBAT") (class "Default")
      (node (ref "BT1") (pin "1") (pinfunction "+_1") (pintype "passive"))
      (node (ref "C9") (pin "1") (pinfunction "1_1") (pintype "passive"))
      (node (ref "R66") (pin "2") (pinfunction "2_2") (pintype "passive"))
      (node (ref "U1") (pin "1") (pinfunction "VBAT_1") (pintype "power_in"))
      (node (ref "VD4") (pin "1") (pinfunction "K_1") (pintype "passive"))
    )
    (net (code "124") (name "VBATI") (class "Default")
      (node (ref "C29") (pin "2") (pinfunction "2_2") (pintype "passive"))
      (node (ref "D2") (pin "3") (pinfunction "Vbat_3") (pintype "power_in"))
      (node (ref "SW10") (pin "2") (pinfunction "2_2") (pintype "passive"))
      (node (ref "X1") (pin "1") (pinfunction "1_1") (pintype "passive"))
    )
    (net (code "125") (name "VBATN") (class "Default")
      (node (ref "D7") (pin "3") (pinfunction "IN+_3") (pintype "passive"))
      (node (ref "R37") (pin "1") (pinfunction "1_1") (pintype "passive"))
      (node (ref "X2") (pin "1") (pinfunction "1_1") (pintype "passive"))
    )
    (net (code "126") (name "VBATO") (class "Default")
      (node (ref "C16") (pin "2") (pinfunction "2_2") (pintype "passive"))
      (node (ref "C17") (pin "2") (pinfunction "2_2") (pintype "passive"))
      (node (ref "J1") (pin "3") (pinfunction "3_3") (pintype "passive"))
      (node (ref "L1") (pin "1") (pinfunction "1_1") (pintype "passive"))
      (node (ref "R7") (pin "1") (pinfunction "1_1") (pintype "passive"))
      (node (ref "SW10") (pin "1") (pinfunction "1_1") (pintype "passive"))
      (node (ref "XT4") (pin "4") (pinfunction "EN_4") (pintype "passive"))
      (node (ref "XT4") (pin "5") (pinfunction "IN_5") (pintype "passive"))
    )
    (net (code "127") (name "VOUT") (class "Default")
      (node (ref "J1") (pin "2") (pinfunction "2_2") (pintype "passive"))
      (node (ref "XT1") (pin "1") (pinfunction "1_1") (pintype "passive"))
      (node (ref "XT3") (pin "1") (pinfunction "1_1") (pintype "passive"))
      (node (ref "XT6") (pin "1") (pinfunction "1_1") (pintype "passive"))
      (node (ref "XT7") (pin "1") (pinfunction "1_1") (pintype "passive"))
    )
    (net (code "128") (name "VUSB") (class "Default")
      (node (ref "C18") (pin "2") (pinfunction "2_2") (pintype "passive"))
      (node (ref "D1") (pin "1") (pinfunction "Vbus_1") (pintype "passive"))
      (node (ref "D2") (pin "4") (pinfunction "Vdd_4") (pintype "passive"))
      (node (ref "R10") (pin "1") (pinfunction "1_1") (pintype "passive"))
      (node (ref "R13") (pin "1") (pinfunction "1_1") (pintype "passive"))
      (node (ref "VD2") (pin "5") (pinfunction "VBUS_5") (pintype "passive"))
    )
    (net (code "129") (name "unconnected-(D1-OTG-Pad4)") (class "Default")
      (node (ref "D1") (pin "4") (pinfunction "OTG_4") (pintype "passive+no_connect"))
    )
    (net (code "130") (name "unconnected-(D3B-2OUT-Pad7)") (class "Default")
      (node (ref "D3") (pin "7") (pinfunction "2OUT_7") (pintype "passive+no_connect"))
    )
    (net (code "131") (name "unconnected-(DA2-DNC-Pad8)") (class "Default")
      (node (ref "DA2") (pin "8") (pinfunction "DNC_8") (pintype "passive+no_connect"))
    )
    (net (code "132") (name "unconnected-(DA3-AUX_CL-Pad7)") (class "Default")
      (node (ref "DA3") (pin "7") (pinfunction "AUX_CL_7") (pintype "passive+no_connect"))
    )
    (net (code "133") (name "unconnected-(DA3-AUX_DA-Pad6)") (class "Default")
      (node (ref "DA3") (pin "6") (pinfunction "AUX_DA_6") (pintype "passive+no_connect"))
    )
    (net (code "134") (name "unconnected-(DA3-RESV-Pad19)") (class "Default")
      (node (ref "DA3") (pin "19") (pinfunction "RESV_19") (pintype "passive+no_connect"))
    )
    (net (code "135") (name "unconnected-(DA3-RESV-Pad21)") (class "Default")
      (node (ref "DA3") (pin "21") (pinfunction "RESV_21") (pintype "passive+no_connect"))
    )
    (net (code "136") (name "unconnected-(DA3-RESV-Pad22)") (class "Default")
      (node (ref "DA3") (pin "22") (pinfunction "RESV_22") (pintype "passive+no_connect"))
    )
    (net (code "137") (name "unconnected-(H1-D3-Pad21)") (class "Default")
      (node (ref "H1") (pin "21") (pinfunction "D3_21") (pintype "passive+no_connect"))
    )
    (net (code "138") (name "unconnected-(H1-D4-Pad22)") (class "Default")
      (node (ref "H1") (pin "22") (pinfunction "D4_22") (pintype "passive+no_connect"))
    )
    (net (code "139") (name "unconnected-(H1-D5-Pad23)") (class "Default")
      (node (ref "H1") (pin "23") (pinfunction "D5_23") (pintype "passive+no_connect"))
    )
    (net (code "140") (name "unconnected-(H1-D6-Pad24)") (class "Default")
      (node (ref "H1") (pin "24") (pinfunction "D6_24") (pintype "passive+no_connect"))
    )
    (net (code "141") (name "unconnected-(H1-D7-Pad25)") (class "Default")
      (node (ref "H1") (pin "25") (pinfunction "D7_25") (pintype "passive+no_connect"))
    )
    (net (code "142") (name "unconnected-(H1-E{slash}RD#-Pad17)") (class "Default")
      (node (ref "H1") (pin "17") (pinfunction "E/RD#_17") (pintype "passive+no_connect"))
    )
    (net (code "143") (name "unconnected-(H1-NC-Pad7)") (class "Default")
      (node (ref "H1") (pin "7") (pinfunction "NC_7") (pintype "passive+no_connect"))
    )
    (net (code "144") (name "unconnected-(H1-R{slash}W#-Pad16)") (class "Default")
      (node (ref "H1") (pin "16") (pinfunction "R/W#_16") (pintype "passive+no_connect"))
    )
    (net (code "145") (name "unconnected-(HL5-Dout-Pad2)") (class "Default")
      (node (ref "HL5") (pin "2") (pinfunction "Dout_2") (pintype "passive+no_connect"))
    )
    (net (code "146") (name "unconnected-(SW10-Pad3)") (class "Default")
      (node (ref "SW10") (pin "3") (pinfunction "3_3") (pintype "passive+no_connect"))
    )
    (net (code "147") (name "unconnected-(U1-PA0-WKUP-Pad14)") (class "Default")
      (node (ref "U1") (pin "14") (pinfunction "PA0-WKUP_14") (pintype "bidirectional"))
    )
    (net (code "148") (name "unconnected-(U1-PC13-TAMPER-RTC-Pad2)") (class "Default")
      (node (ref "U1") (pin "2") (pinfunction "PC13-TAMPER-RTC_2") (pintype "bidirectional+no_connect"))
    )
    (net (code "149") (name "unconnected-(XT4-NC-Pad6)") (class "Default")
      (node (ref "XT4") (pin "6") (pinfunction "NC_6") (pintype "passive+no_connect"))
    )
  )
)
